# Payload-A.net
KiCad netlist of a schematic drawn in EAGLE
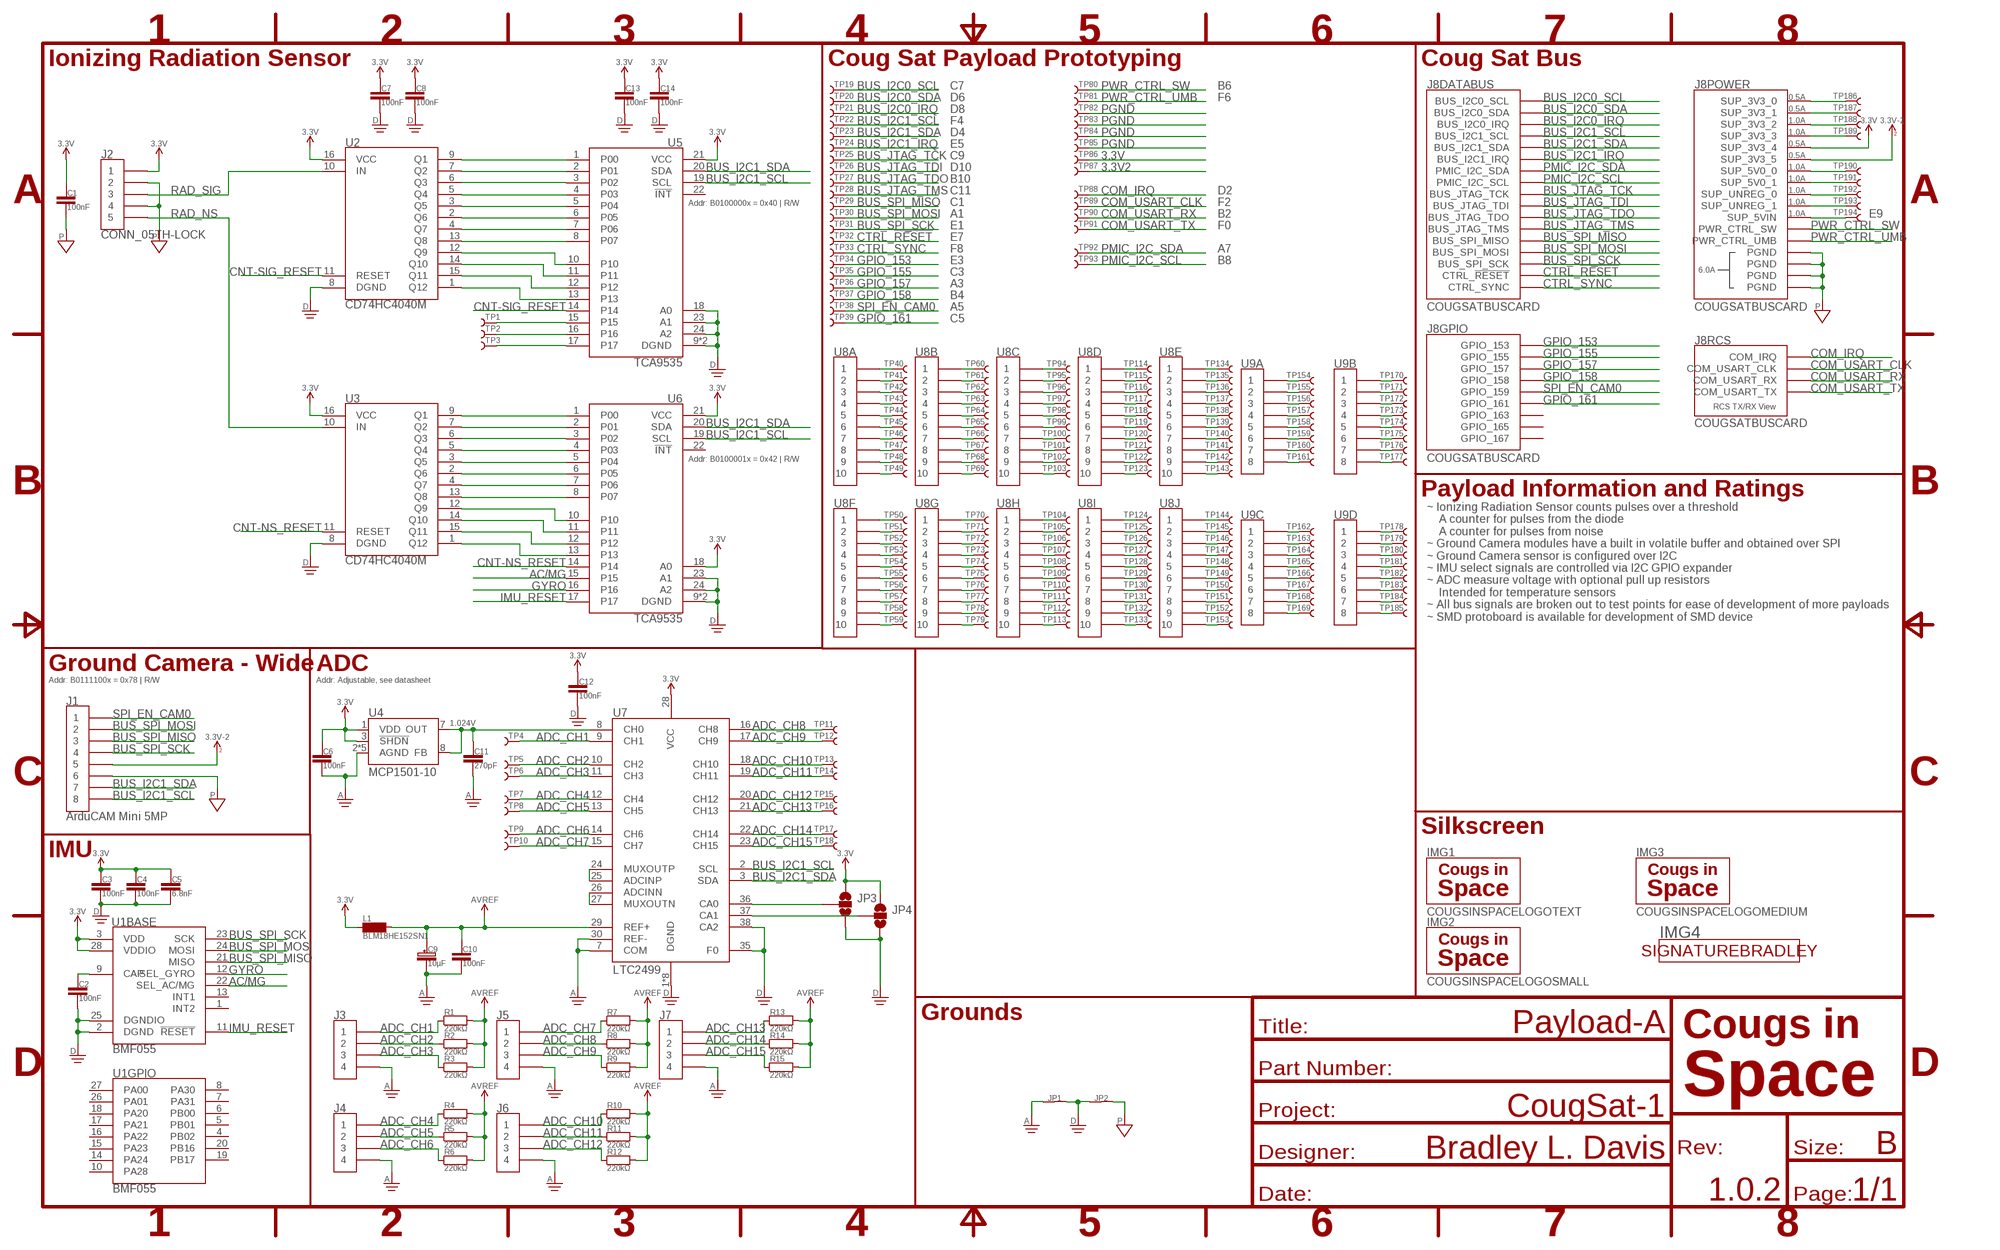
[diagram p0: schematic, sheet 1]

(export (version "E")
  (design (tool "Eeschema 10.0.6"))
  (components
    (comp (ref "C1")
      (value "100nF")
      (footprint "eagle-import:1608")
      (libsource (lib "eagle-import") (part "CAPACITOR1608"))
    )
    (comp (ref "C2")
      (value "100nF")
      (footprint "eagle-import:1608")
      (libsource (lib "eagle-import") (part "CougsInSpace_497568_CAPACITOR1608"))
    )
    (comp (ref "C3")
      (value "100nF")
      (footprint "eagle-import:1608")
      (libsource (lib "eagle-import") (part "CougsInSpace_497568_CAPACITOR1608"))
    )
    (comp (ref "C4")
      (value "100nF")
      (footprint "eagle-import:1608")
      (libsource (lib "eagle-import") (part "CougsInSpace_497568_CAPACITOR1608"))
    )
    (comp (ref "C5")
      (value "6.8nF")
      (footprint "eagle-import:1608")
      (libsource (lib "eagle-import") (part "CougsInSpace_497568_CAPACITOR1608"))
    )
    (comp (ref "C6")
      (value "100nF")
      (footprint "eagle-import:1608")
      (libsource (lib "eagle-import") (part "CougsInSpace_497568_CAPACITOR1608"))
    )
    (comp (ref "C7")
      (value "100nF")
      (footprint "eagle-import:1608")
      (libsource (lib "eagle-import") (part "CAPACITOR1608"))
    )
    (comp (ref "C8")
      (value "100nF")
      (footprint "eagle-import:1608")
      (libsource (lib "eagle-import") (part "CAPACITOR1608"))
    )
    (comp (ref "C9")
      (value "10µF")
      (footprint "eagle-import:4028-POL")
      (libsource (lib "eagle-import") (part "CAPACITOR-POLARIZED4028"))
    )
    (comp (ref "C10")
      (value "100nF")
      (footprint "eagle-import:1608")
      (libsource (lib "eagle-import") (part "CougsInSpace_497568_CAPACITOR1608"))
    )
    (comp (ref "C11")
      (value "270pF")
      (footprint "eagle-import:1608")
      (libsource (lib "eagle-import") (part "CougsInSpace_497568_CAPACITOR1608"))
    )
    (comp (ref "C12")
      (value "100nF")
      (footprint "eagle-import:3216")
      (libsource (lib "eagle-import") (part "CougsInSpace_497568_CAPACITOR3216"))
    )
    (comp (ref "C13")
      (value "100nF")
      (footprint "eagle-import:1608")
      (libsource (lib "eagle-import") (part "CAPACITOR1608"))
    )
    (comp (ref "C14")
      (value "100nF")
      (footprint "eagle-import:1608")
      (libsource (lib "eagle-import") (part "CAPACITOR1608"))
    )
    (comp (ref "IMG1")
      (value "COUGSINSPACELOGOTEXT")
      (footprint "eagle-import:COUGSINSPACETEXT")
      (libsource (lib "eagle-import") (part "COUGSINSPACELOGOTEXT"))
    )
    (comp (ref "IMG2")
      (value "COUGSINSPACELOGOSMALL")
      (footprint "eagle-import:COUGSINSPACELOGO_SMALL")
      (libsource (lib "eagle-import") (part "COUGSINSPACELOGOSMALL"))
    )
    (comp (ref "IMG3")
      (value "COUGSINSPACELOGOMEDIUM")
      (footprint "eagle-import:COUGSINSPACELOGO_MEDIUM")
      (libsource (lib "eagle-import") (part "COUGSINSPACELOGOMEDIUM"))
    )
    (comp (ref "IMG4")
      (value "SIGNATUREBRADLEY")
      (footprint "eagle-import:SIGNATURE-BRADLEY")
      (libsource (lib "eagle-import") (part "SIGNATUREBRADLEY"))
    )
    (comp (ref "J1")
      (value "ArduCAM Mini 5MP")
      (footprint "eagle-import:1X08_LOCK")
      (libsource (lib "eagle-import") (part "CONN_08TH-LOCK"))
    )
    (comp (ref "J2")
      (value "CONN_05TH-LOCK")
      (footprint "eagle-import:1X05_LOCK")
      (libsource (lib "eagle-import") (part "CONN_05TH-LOCK"))
    )
    (comp (ref "J3")
      (value "CONN_04PICOLOCK1.5MM")
      (footprint "eagle-import:1X04_PICOLOCK1.5MM")
      (libsource (lib "eagle-import") (part "CONN_04PICOLOCK1.5MM"))
    )
    (comp (ref "J4")
      (value "CONN_04PICOLOCK1.5MM")
      (footprint "eagle-import:1X04_PICOLOCK1.5MM")
      (libsource (lib "eagle-import") (part "CONN_04PICOLOCK1.5MM"))
    )
    (comp (ref "J5")
      (value "CONN_04PICOLOCK1.5MM")
      (footprint "eagle-import:1X04_PICOLOCK1.5MM")
      (libsource (lib "eagle-import") (part "CONN_04PICOLOCK1.5MM"))
    )
    (comp (ref "J6")
      (value "CONN_04PICOLOCK1.5MM")
      (footprint "eagle-import:1X04_PICOLOCK1.5MM")
      (libsource (lib "eagle-import") (part "CONN_04PICOLOCK1.5MM"))
    )
    (comp (ref "J7")
      (value "CONN_04PICOLOCK1.5MM")
      (footprint "eagle-import:1X04_PICOLOCK1.5MM")
      (libsource (lib "eagle-import") (part "CONN_04PICOLOCK1.5MM"))
    )
    (comp (ref "J8")
      (value "COUGSATBUSCARD")
      (footprint "eagle-import:COUGSATBUS_MALE-SODIMM")
      (libsource (lib "eagle-import") (part "COUGSATBUSCARD"))
    )
    (comp (ref "JP1")
      (value "SHORTCIRCUIT1608JUMPER")
      (footprint "eagle-import:1608")
      (libsource (lib "eagle-import") (part "SHORTCIRCUIT1608JUMPER"))
    )
    (comp (ref "JP2")
      (value "SHORTCIRCUIT1608JUMPER")
      (footprint "eagle-import:1608")
      (libsource (lib "eagle-import") (part "SHORTCIRCUIT1608JUMPER"))
    )
    (comp (ref "JP3")
      (value "JUMPER-SMT_3_NO_SILK")
      (footprint "eagle-import:SMT-JUMPER_3_NO_SILK")
      (libsource (lib "eagle-import") (part "JUMPER-SMT_3_NO_SILK"))
    )
    (comp (ref "JP4")
      (value "JUMPER-SMT_3_NO_SILK")
      (footprint "eagle-import:SMT-JUMPER_3_NO_SILK")
      (libsource (lib "eagle-import") (part "JUMPER-SMT_3_NO_SILK"))
    )
    (comp (ref "L1")
      (value "BLM18HE152SN1")
      (footprint "eagle-import:1608")
      (libsource (lib "eagle-import") (part "INDUCTOR1608"))
    )
    (comp (ref "R1")
      (value "220kΩ")
      (footprint "eagle-import:1608")
      (libsource (lib "eagle-import") (part "RESISTOR1608"))
    )
    (comp (ref "R2")
      (value "220kΩ")
      (footprint "eagle-import:1608")
      (libsource (lib "eagle-import") (part "RESISTOR1608"))
    )
    (comp (ref "R3")
      (value "220kΩ")
      (footprint "eagle-import:1608")
      (libsource (lib "eagle-import") (part "RESISTOR1608"))
    )
    (comp (ref "R4")
      (value "220kΩ")
      (footprint "eagle-import:1608")
      (libsource (lib "eagle-import") (part "RESISTOR1608"))
    )
    (comp (ref "R5")
      (value "220kΩ")
      (footprint "eagle-import:1608")
      (libsource (lib "eagle-import") (part "RESISTOR1608"))
    )
    (comp (ref "R6")
      (value "220kΩ")
      (footprint "eagle-import:1608")
      (libsource (lib "eagle-import") (part "RESISTOR1608"))
    )
    (comp (ref "R7")
      (value "220kΩ")
      (footprint "eagle-import:1608")
      (libsource (lib "eagle-import") (part "RESISTOR1608"))
    )
    (comp (ref "R8")
      (value "220kΩ")
      (footprint "eagle-import:1608")
      (libsource (lib "eagle-import") (part "RESISTOR1608"))
    )
    (comp (ref "R9")
      (value "220kΩ")
      (footprint "eagle-import:1608")
      (libsource (lib "eagle-import") (part "RESISTOR1608"))
    )
    (comp (ref "R10")
      (value "220kΩ")
      (footprint "eagle-import:1608")
      (libsource (lib "eagle-import") (part "RESISTOR1608"))
    )
    (comp (ref "R11")
      (value "220kΩ")
      (footprint "eagle-import:1608")
      (libsource (lib "eagle-import") (part "RESISTOR1608"))
    )
    (comp (ref "R12")
      (value "220kΩ")
      (footprint "eagle-import:1608")
      (libsource (lib "eagle-import") (part "RESISTOR1608"))
    )
    (comp (ref "R13")
      (value "220kΩ")
      (footprint "eagle-import:1608")
      (libsource (lib "eagle-import") (part "RESISTOR1608"))
    )
    (comp (ref "R14")
      (value "220kΩ")
      (footprint "eagle-import:1608")
      (libsource (lib "eagle-import") (part "RESISTOR1608"))
    )
    (comp (ref "R15")
      (value "220kΩ")
      (footprint "eagle-import:1608")
      (libsource (lib "eagle-import") (part "RESISTOR1608"))
    )
    (comp (ref "TP1")
      (value "TEST-POINT1.25MM")
      (footprint "eagle-import:PAD1.25X1.25")
      (libsource (lib "eagle-import") (part "TEST-POINT1.25MM"))
    )
    (comp (ref "TP2")
      (value "TEST-POINT1.25MM")
      (footprint "eagle-import:PAD1.25X1.25")
      (libsource (lib "eagle-import") (part "TEST-POINT1.25MM"))
    )
    (comp (ref "TP3")
      (value "TEST-POINT1.25MM")
      (footprint "eagle-import:PAD1.25X1.25")
      (libsource (lib "eagle-import") (part "TEST-POINT1.25MM"))
    )
    (comp (ref "TP4")
      (value "TEST-POINT1.25MM")
      (footprint "eagle-import:PAD1.25X1.25")
      (libsource (lib "eagle-import") (part "TEST-POINT1.25MM"))
    )
    (comp (ref "TP5")
      (value "TEST-POINT1.25MM")
      (footprint "eagle-import:PAD1.25X1.25")
      (libsource (lib "eagle-import") (part "TEST-POINT1.25MM"))
    )
    (comp (ref "TP6")
      (value "TEST-POINT1.25MM")
      (footprint "eagle-import:PAD1.25X1.25")
      (libsource (lib "eagle-import") (part "TEST-POINT1.25MM"))
    )
    (comp (ref "TP7")
      (value "TEST-POINT1.25MM")
      (footprint "eagle-import:PAD1.25X1.25")
      (libsource (lib "eagle-import") (part "TEST-POINT1.25MM"))
    )
    (comp (ref "TP8")
      (value "TEST-POINT1.25MM")
      (footprint "eagle-import:PAD1.25X1.25")
      (libsource (lib "eagle-import") (part "TEST-POINT1.25MM"))
    )
    (comp (ref "TP9")
      (value "TEST-POINT1.25MM")
      (footprint "eagle-import:PAD1.25X1.25")
      (libsource (lib "eagle-import") (part "TEST-POINT1.25MM"))
    )
    (comp (ref "TP10")
      (value "TEST-POINT1.25MM")
      (footprint "eagle-import:PAD1.25X1.25")
      (libsource (lib "eagle-import") (part "TEST-POINT1.25MM"))
    )
    (comp (ref "TP11")
      (value "TEST-POINT1.25MM")
      (footprint "eagle-import:PAD1.25X1.25")
      (libsource (lib "eagle-import") (part "TEST-POINT1.25MM"))
    )
    (comp (ref "TP12")
      (value "TEST-POINT1.25MM")
      (footprint "eagle-import:PAD1.25X1.25")
      (libsource (lib "eagle-import") (part "TEST-POINT1.25MM"))
    )
    (comp (ref "TP13")
      (value "TEST-POINT1.25MM")
      (footprint "eagle-import:PAD1.25X1.25")
      (libsource (lib "eagle-import") (part "TEST-POINT1.25MM"))
    )
    (comp (ref "TP14")
      (value "TEST-POINT1.25MM")
      (footprint "eagle-import:PAD1.25X1.25")
      (libsource (lib "eagle-import") (part "TEST-POINT1.25MM"))
    )
    (comp (ref "TP15")
      (value "TEST-POINT1.25MM")
      (footprint "eagle-import:PAD1.25X1.25")
      (libsource (lib "eagle-import") (part "TEST-POINT1.25MM"))
    )
    (comp (ref "TP16")
      (value "TEST-POINT1.25MM")
      (footprint "eagle-import:PAD1.25X1.25")
      (libsource (lib "eagle-import") (part "TEST-POINT1.25MM"))
    )
    (comp (ref "TP17")
      (value "TEST-POINT1.25MM")
      (footprint "eagle-import:PAD1.25X1.25")
      (libsource (lib "eagle-import") (part "TEST-POINT1.25MM"))
    )
    (comp (ref "TP18")
      (value "TEST-POINT1.25MM")
      (footprint "eagle-import:PAD1.25X1.25")
      (libsource (lib "eagle-import") (part "TEST-POINT1.25MM"))
    )
    (comp (ref "TP19")
      (value "TEST-POINT1.25MM")
      (footprint "eagle-import:PAD1.25X1.25")
      (libsource (lib "eagle-import") (part "TEST-POINT1.25MM"))
    )
    (comp (ref "TP20")
      (value "TEST-POINT1.25MM")
      (footprint "eagle-import:PAD1.25X1.25")
      (libsource (lib "eagle-import") (part "TEST-POINT1.25MM"))
    )
    (comp (ref "TP21")
      (value "TEST-POINT1.25MM")
      (footprint "eagle-import:PAD1.25X1.25")
      (libsource (lib "eagle-import") (part "TEST-POINT1.25MM"))
    )
    (comp (ref "TP22")
      (value "TEST-POINT1.25MM")
      (footprint "eagle-import:PAD1.25X1.25")
      (libsource (lib "eagle-import") (part "TEST-POINT1.25MM"))
    )
    (comp (ref "TP23")
      (value "TEST-POINT1.25MM")
      (footprint "eagle-import:PAD1.25X1.25")
      (libsource (lib "eagle-import") (part "TEST-POINT1.25MM"))
    )
    (comp (ref "TP24")
      (value "TEST-POINT1.25MM")
      (footprint "eagle-import:PAD1.25X1.25")
      (libsource (lib "eagle-import") (part "TEST-POINT1.25MM"))
    )
    (comp (ref "TP25")
      (value "TEST-POINT1.25MM")
      (footprint "eagle-import:PAD1.25X1.25")
      (libsource (lib "eagle-import") (part "TEST-POINT1.25MM"))
    )
    (comp (ref "TP26")
      (value "TEST-POINT1.25MM")
      (footprint "eagle-import:PAD1.25X1.25")
      (libsource (lib "eagle-import") (part "TEST-POINT1.25MM"))
    )
    (comp (ref "TP27")
      (value "TEST-POINT1.25MM")
      (footprint "eagle-import:PAD1.25X1.25")
      (libsource (lib "eagle-import") (part "TEST-POINT1.25MM"))
    )
    (comp (ref "TP28")
      (value "TEST-POINT1.25MM")
      (footprint "eagle-import:PAD1.25X1.25")
      (libsource (lib "eagle-import") (part "TEST-POINT1.25MM"))
    )
    (comp (ref "TP29")
      (value "TEST-POINT1.25MM")
      (footprint "eagle-import:PAD1.25X1.25")
      (libsource (lib "eagle-import") (part "TEST-POINT1.25MM"))
    )
    (comp (ref "TP30")
      (value "TEST-POINT1.25MM")
      (footprint "eagle-import:PAD1.25X1.25")
      (libsource (lib "eagle-import") (part "TEST-POINT1.25MM"))
    )
    (comp (ref "TP31")
      (value "TEST-POINT1.25MM")
      (footprint "eagle-import:PAD1.25X1.25")
      (libsource (lib "eagle-import") (part "TEST-POINT1.25MM"))
    )
    (comp (ref "TP32")
      (value "TEST-POINT1.25MM")
      (footprint "eagle-import:PAD1.25X1.25")
      (libsource (lib "eagle-import") (part "TEST-POINT1.25MM"))
    )
    (comp (ref "TP33")
      (value "TEST-POINT1.25MM")
      (footprint "eagle-import:PAD1.25X1.25")
      (libsource (lib "eagle-import") (part "TEST-POINT1.25MM"))
    )
    (comp (ref "TP34")
      (value "TEST-POINT1.25MM")
      (footprint "eagle-import:PAD1.25X1.25")
      (libsource (lib "eagle-import") (part "TEST-POINT1.25MM"))
    )
    (comp (ref "TP35")
      (value "TEST-POINT1.25MM")
      (footprint "eagle-import:PAD1.25X1.25")
      (libsource (lib "eagle-import") (part "TEST-POINT1.25MM"))
    )
    (comp (ref "TP36")
      (value "TEST-POINT1.25MM")
      (footprint "eagle-import:PAD1.25X1.25")
      (libsource (lib "eagle-import") (part "TEST-POINT1.25MM"))
    )
    (comp (ref "TP37")
      (value "TEST-POINT1.25MM")
      (footprint "eagle-import:PAD1.25X1.25")
      (libsource (lib "eagle-import") (part "TEST-POINT1.25MM"))
    )
    (comp (ref "TP38")
      (value "TEST-POINT1.25MM")
      (footprint "eagle-import:PAD1.25X1.25")
      (libsource (lib "eagle-import") (part "TEST-POINT1.25MM"))
    )
    (comp (ref "TP39")
      (value "TEST-POINT1.25MM")
      (footprint "eagle-import:PAD1.25X1.25")
      (libsource (lib "eagle-import") (part "TEST-POINT1.25MM"))
    )
    (comp (ref "TP40")
      (value "TEST-POINT1MM")
      (footprint "eagle-import:PAD1X1")
      (libsource (lib "eagle-import") (part "TEST-POINT1MM"))
    )
    (comp (ref "TP41")
      (value "TEST-POINT1MM")
      (footprint "eagle-import:PAD1X1")
      (libsource (lib "eagle-import") (part "TEST-POINT1MM"))
    )
    (comp (ref "TP42")
      (value "TEST-POINT1MM")
      (footprint "eagle-import:PAD1X1")
      (libsource (lib "eagle-import") (part "TEST-POINT1MM"))
    )
    (comp (ref "TP43")
      (value "TEST-POINT1MM")
      (footprint "eagle-import:PAD1X1")
      (libsource (lib "eagle-import") (part "TEST-POINT1MM"))
    )
    (comp (ref "TP44")
      (value "TEST-POINT1MM")
      (footprint "eagle-import:PAD1X1")
      (libsource (lib "eagle-import") (part "TEST-POINT1MM"))
    )
    (comp (ref "TP45")
      (value "TEST-POINT1MM")
      (footprint "eagle-import:PAD1X1")
      (libsource (lib "eagle-import") (part "TEST-POINT1MM"))
    )
    (comp (ref "TP46")
      (value "TEST-POINT1MM")
      (footprint "eagle-import:PAD1X1")
      (libsource (lib "eagle-import") (part "TEST-POINT1MM"))
    )
    (comp (ref "TP47")
      (value "TEST-POINT1MM")
      (footprint "eagle-import:PAD1X1")
      (libsource (lib "eagle-import") (part "TEST-POINT1MM"))
    )
    (comp (ref "TP48")
      (value "TEST-POINT1MM")
      (footprint "eagle-import:PAD1X1")
      (libsource (lib "eagle-import") (part "TEST-POINT1MM"))
    )
    (comp (ref "TP49")
      (value "TEST-POINT1MM")
      (footprint "eagle-import:PAD1X1")
      (libsource (lib "eagle-import") (part "TEST-POINT1MM"))
    )
    (comp (ref "TP50")
      (value "TEST-POINT1MM")
      (footprint "eagle-import:PAD1X1")
      (libsource (lib "eagle-import") (part "TEST-POINT1MM"))
    )
    (comp (ref "TP51")
      (value "TEST-POINT1MM")
      (footprint "eagle-import:PAD1X1")
      (libsource (lib "eagle-import") (part "TEST-POINT1MM"))
    )
    (comp (ref "TP52")
      (value "TEST-POINT1MM")
      (footprint "eagle-import:PAD1X1")
      (libsource (lib "eagle-import") (part "TEST-POINT1MM"))
    )
    (comp (ref "TP53")
      (value "TEST-POINT1MM")
      (footprint "eagle-import:PAD1X1")
      (libsource (lib "eagle-import") (part "TEST-POINT1MM"))
    )
    (comp (ref "TP54")
      (value "TEST-POINT1MM")
      (footprint "eagle-import:PAD1X1")
      (libsource (lib "eagle-import") (part "TEST-POINT1MM"))
    )
    (comp (ref "TP55")
      (value "TEST-POINT1MM")
      (footprint "eagle-import:PAD1X1")
      (libsource (lib "eagle-import") (part "TEST-POINT1MM"))
    )
    (comp (ref "TP56")
      (value "TEST-POINT1MM")
      (footprint "eagle-import:PAD1X1")
      (libsource (lib "eagle-import") (part "TEST-POINT1MM"))
    )
    (comp (ref "TP57")
      (value "TEST-POINT1MM")
      (footprint "eagle-import:PAD1X1")
      (libsource (lib "eagle-import") (part "TEST-POINT1MM"))
    )
    (comp (ref "TP58")
      (value "TEST-POINT1MM")
      (footprint "eagle-import:PAD1X1")
      (libsource (lib "eagle-import") (part "TEST-POINT1MM"))
    )
    (comp (ref "TP59")
      (value "TEST-POINT1MM")
      (footprint "eagle-import:PAD1X1")
      (libsource (lib "eagle-import") (part "TEST-POINT1MM"))
    )
    (comp (ref "TP60")
      (value "TEST-POINT1MM")
      (footprint "eagle-import:PAD1X1")
      (libsource (lib "eagle-import") (part "TEST-POINT1MM"))
    )
    (comp (ref "TP61")
      (value "TEST-POINT1MM")
      (footprint "eagle-import:PAD1X1")
      (libsource (lib "eagle-import") (part "TEST-POINT1MM"))
    )
    (comp (ref "TP62")
      (value "TEST-POINT1MM")
      (footprint "eagle-import:PAD1X1")
      (libsource (lib "eagle-import") (part "TEST-POINT1MM"))
    )
    (comp (ref "TP63")
      (value "TEST-POINT1MM")
      (footprint "eagle-import:PAD1X1")
      (libsource (lib "eagle-import") (part "TEST-POINT1MM"))
    )
    (comp (ref "TP64")
      (value "TEST-POINT1MM")
      (footprint "eagle-import:PAD1X1")
      (libsource (lib "eagle-import") (part "TEST-POINT1MM"))
    )
    (comp (ref "TP65")
      (value "TEST-POINT1MM")
      (footprint "eagle-import:PAD1X1")
      (libsource (lib "eagle-import") (part "TEST-POINT1MM"))
    )
    (comp (ref "TP66")
      (value "TEST-POINT1MM")
      (footprint "eagle-import:PAD1X1")
      (libsource (lib "eagle-import") (part "TEST-POINT1MM"))
    )
    (comp (ref "TP67")
      (value "TEST-POINT1MM")
      (footprint "eagle-import:PAD1X1")
      (libsource (lib "eagle-import") (part "TEST-POINT1MM"))
    )
    (comp (ref "TP68")
      (value "TEST-POINT1MM")
      (footprint "eagle-import:PAD1X1")
      (libsource (lib "eagle-import") (part "TEST-POINT1MM"))
    )
    (comp (ref "TP69")
      (value "TEST-POINT1MM")
      (footprint "eagle-import:PAD1X1")
      (libsource (lib "eagle-import") (part "TEST-POINT1MM"))
    )
    (comp (ref "TP70")
      (value "TEST-POINT1MM")
      (footprint "eagle-import:PAD1X1")
      (libsource (lib "eagle-import") (part "TEST-POINT1MM"))
    )
    (comp (ref "TP71")
      (value "TEST-POINT1MM")
      (footprint "eagle-import:PAD1X1")
      (libsource (lib "eagle-import") (part "TEST-POINT1MM"))
    )
    (comp (ref "TP72")
      (value "TEST-POINT1MM")
      (footprint "eagle-import:PAD1X1")
      (libsource (lib "eagle-import") (part "TEST-POINT1MM"))
    )
    (comp (ref "TP73")
      (value "TEST-POINT1MM")
      (footprint "eagle-import:PAD1X1")
      (libsource (lib "eagle-import") (part "TEST-POINT1MM"))
    )
    (comp (ref "TP74")
      (value "TEST-POINT1MM")
      (footprint "eagle-import:PAD1X1")
      (libsource (lib "eagle-import") (part "TEST-POINT1MM"))
    )
    (comp (ref "TP75")
      (value "TEST-POINT1MM")
      (footprint "eagle-import:PAD1X1")
      (libsource (lib "eagle-import") (part "TEST-POINT1MM"))
    )
    (comp (ref "TP76")
      (value "TEST-POINT1MM")
      (footprint "eagle-import:PAD1X1")
      (libsource (lib "eagle-import") (part "TEST-POINT1MM"))
    )
    (comp (ref "TP77")
      (value "TEST-POINT1MM")
      (footprint "eagle-import:PAD1X1")
      (libsource (lib "eagle-import") (part "TEST-POINT1MM"))
    )
    (comp (ref "TP78")
      (value "TEST-POINT1MM")
      (footprint "eagle-import:PAD1X1")
      (libsource (lib "eagle-import") (part "TEST-POINT1MM"))
    )
    (comp (ref "TP79")
      (value "TEST-POINT1MM")
      (footprint "eagle-import:PAD1X1")
      (libsource (lib "eagle-import") (part "TEST-POINT1MM"))
    )
    (comp (ref "TP80")
      (value "TEST-POINT1.25MM")
      (footprint "eagle-import:PAD1.25X1.25")
      (libsource (lib "eagle-import") (part "TEST-POINT1.25MM"))
    )
    (comp (ref "TP81")
      (value "TEST-POINT1.25MM")
      (footprint "eagle-import:PAD1.25X1.25")
      (libsource (lib "eagle-import") (part "TEST-POINT1.25MM"))
    )
    (comp (ref "TP82")
      (value "TEST-POINT1.25MM")
      (footprint "eagle-import:PAD1.25X1.25")
      (libsource (lib "eagle-import") (part "TEST-POINT1.25MM"))
    )
    (comp (ref "TP83")
      (value "TEST-POINT1.25MM")
      (footprint "eagle-import:PAD1.25X1.25")
      (libsource (lib "eagle-import") (part "TEST-POINT1.25MM"))
    )
    (comp (ref "TP84")
      (value "TEST-POINT1.25MM")
      (footprint "eagle-import:PAD1.25X1.25")
      (libsource (lib "eagle-import") (part "TEST-POINT1.25MM"))
    )
    (comp (ref "TP85")
      (value "TEST-POINT1.25MM")
      (footprint "eagle-import:PAD1.25X1.25")
      (libsource (lib "eagle-import") (part "TEST-POINT1.25MM"))
    )
    (comp (ref "TP86")
      (value "TEST-POINT1.25MM")
      (footprint "eagle-import:PAD1.25X1.25")
      (libsource (lib "eagle-import") (part "TEST-POINT1.25MM"))
    )
    (comp (ref "TP87")
      (value "TEST-POINT1.25MM")
      (footprint "eagle-import:PAD1.25X1.25")
      (libsource (lib "eagle-import") (part "TEST-POINT1.25MM"))
    )
    (comp (ref "TP88")
      (value "TEST-POINT1.25MM")
      (footprint "eagle-import:PAD1.25X1.25")
      (libsource (lib "eagle-import") (part "TEST-POINT1.25MM"))
    )
    (comp (ref "TP89")
      (value "TEST-POINT1.25MM")
      (footprint "eagle-import:PAD1.25X1.25")
      (libsource (lib "eagle-import") (part "TEST-POINT1.25MM"))
    )
    (comp (ref "TP90")
      (value "TEST-POINT1.25MM")
      (footprint "eagle-import:PAD1.25X1.25")
      (libsource (lib "eagle-import") (part "TEST-POINT1.25MM"))
    )
    (comp (ref "TP91")
      (value "TEST-POINT1.25MM")
      (footprint "eagle-import:PAD1.25X1.25")
      (libsource (lib "eagle-import") (part "TEST-POINT1.25MM"))
    )
    (comp (ref "TP92")
      (value "TEST-POINT1.25MM")
      (footprint "eagle-import:PAD1.25X1.25")
      (libsource (lib "eagle-import") (part "TEST-POINT1.25MM"))
    )
    (comp (ref "TP93")
      (value "TEST-POINT1.25MM")
      (footprint "eagle-import:PAD1.25X1.25")
      (libsource (lib "eagle-import") (part "TEST-POINT1.25MM"))
    )
    (comp (ref "TP94")
      (value "TEST-POINT1MM")
      (footprint "eagle-import:PAD1X1")
      (libsource (lib "eagle-import") (part "TEST-POINT1MM"))
    )
    (comp (ref "TP95")
      (value "TEST-POINT1MM")
      (footprint "eagle-import:PAD1X1")
      (libsource (lib "eagle-import") (part "TEST-POINT1MM"))
    )
    (comp (ref "TP96")
      (value "TEST-POINT1MM")
      (footprint "eagle-import:PAD1X1")
      (libsource (lib "eagle-import") (part "TEST-POINT1MM"))
    )
    (comp (ref "TP97")
      (value "TEST-POINT1MM")
      (footprint "eagle-import:PAD1X1")
      (libsource (lib "eagle-import") (part "TEST-POINT1MM"))
    )
    (comp (ref "TP98")
      (value "TEST-POINT1MM")
      (footprint "eagle-import:PAD1X1")
      (libsource (lib "eagle-import") (part "TEST-POINT1MM"))
    )
    (comp (ref "TP99")
      (value "TEST-POINT1MM")
      (footprint "eagle-import:PAD1X1")
      (libsource (lib "eagle-import") (part "TEST-POINT1MM"))
    )
    (comp (ref "TP100")
      (value "TEST-POINT1MM")
      (footprint "eagle-import:PAD1X1")
      (libsource (lib "eagle-import") (part "TEST-POINT1MM"))
    )
    (comp (ref "TP101")
      (value "TEST-POINT1MM")
      (footprint "eagle-import:PAD1X1")
      (libsource (lib "eagle-import") (part "TEST-POINT1MM"))
    )
    (comp (ref "TP102")
      (value "TEST-POINT1MM")
      (footprint "eagle-import:PAD1X1")
      (libsource (lib "eagle-import") (part "TEST-POINT1MM"))
    )
    (comp (ref "TP103")
      (value "TEST-POINT1MM")
      (footprint "eagle-import:PAD1X1")
      (libsource (lib "eagle-import") (part "TEST-POINT1MM"))
    )
    (comp (ref "TP104")
      (value "TEST-POINT1MM")
      (footprint "eagle-import:PAD1X1")
      (libsource (lib "eagle-import") (part "TEST-POINT1MM"))
    )
    (comp (ref "TP105")
      (value "TEST-POINT1MM")
      (footprint "eagle-import:PAD1X1")
      (libsource (lib "eagle-import") (part "TEST-POINT1MM"))
    )
    (comp (ref "TP106")
      (value "TEST-POINT1MM")
      (footprint "eagle-import:PAD1X1")
      (libsource (lib "eagle-import") (part "TEST-POINT1MM"))
    )
    (comp (ref "TP107")
      (value "TEST-POINT1MM")
      (footprint "eagle-import:PAD1X1")
      (libsource (lib "eagle-import") (part "TEST-POINT1MM"))
    )
    (comp (ref "TP108")
      (value "TEST-POINT1MM")
      (footprint "eagle-import:PAD1X1")
      (libsource (lib "eagle-import") (part "TEST-POINT1MM"))
    )
    (comp (ref "TP109")
      (value "TEST-POINT1MM")
      (footprint "eagle-import:PAD1X1")
      (libsource (lib "eagle-import") (part "TEST-POINT1MM"))
    )
    (comp (ref "TP110")
      (value "TEST-POINT1MM")
      (footprint "eagle-import:PAD1X1")
      (libsource (lib "eagle-import") (part "TEST-POINT1MM"))
    )
    (comp (ref "TP111")
      (value "TEST-POINT1MM")
      (footprint "eagle-import:PAD1X1")
      (libsource (lib "eagle-import") (part "TEST-POINT1MM"))
    )
    (comp (ref "TP112")
      (value "TEST-POINT1MM")
      (footprint "eagle-import:PAD1X1")
      (libsource (lib "eagle-import") (part "TEST-POINT1MM"))
    )
    (comp (ref "TP113")
      (value "TEST-POINT1MM")
      (footprint "eagle-import:PAD1X1")
      (libsource (lib "eagle-import") (part "TEST-POINT1MM"))
    )
    (comp (ref "TP114")
      (value "TEST-POINT1MM")
      (footprint "eagle-import:PAD1X1")
      (libsource (lib "eagle-import") (part "TEST-POINT1MM"))
    )
    (comp (ref "TP115")
      (value "TEST-POINT1MM")
      (footprint "eagle-import:PAD1X1")
      (libsource (lib "eagle-import") (part "TEST-POINT1MM"))
    )
    (comp (ref "TP116")
      (value "TEST-POINT1MM")
      (footprint "eagle-import:PAD1X1")
      (libsource (lib "eagle-import") (part "TEST-POINT1MM"))
    )
    (comp (ref "TP117")
      (value "TEST-POINT1MM")
      (footprint "eagle-import:PAD1X1")
      (libsource (lib "eagle-import") (part "TEST-POINT1MM"))
    )
    (comp (ref "TP118")
      (value "TEST-POINT1MM")
      (footprint "eagle-import:PAD1X1")
      (libsource (lib "eagle-import") (part "TEST-POINT1MM"))
    )
    (comp (ref "TP119")
      (value "TEST-POINT1MM")
      (footprint "eagle-import:PAD1X1")
      (libsource (lib "eagle-import") (part "TEST-POINT1MM"))
    )
    (comp (ref "TP120")
      (value "TEST-POINT1MM")
      (footprint "eagle-import:PAD1X1")
      (libsource (lib "eagle-import") (part "TEST-POINT1MM"))
    )
    (comp (ref "TP121")
      (value "TEST-POINT1MM")
      (footprint "eagle-import:PAD1X1")
      (libsource (lib "eagle-import") (part "TEST-POINT1MM"))
    )
    (comp (ref "TP122")
      (value "TEST-POINT1MM")
      (footprint "eagle-import:PAD1X1")
      (libsource (lib "eagle-import") (part "TEST-POINT1MM"))
    )
    (comp (ref "TP123")
      (value "TEST-POINT1MM")
      (footprint "eagle-import:PAD1X1")
      (libsource (lib "eagle-import") (part "TEST-POINT1MM"))
    )
    (comp (ref "TP124")
      (value "TEST-POINT1MM")
      (footprint "eagle-import:PAD1X1")
      (libsource (lib "eagle-import") (part "TEST-POINT1MM"))
    )
    (comp (ref "TP125")
      (value "TEST-POINT1MM")
      (footprint "eagle-import:PAD1X1")
      (libsource (lib "eagle-import") (part "TEST-POINT1MM"))
    )
    (comp (ref "TP126")
      (value "TEST-POINT1MM")
      (footprint "eagle-import:PAD1X1")
      (libsource (lib "eagle-import") (part "TEST-POINT1MM"))
    )
    (comp (ref "TP127")
      (value "TEST-POINT1MM")
      (footprint "eagle-import:PAD1X1")
      (libsource (lib "eagle-import") (part "TEST-POINT1MM"))
    )
    (comp (ref "TP128")
      (value "TEST-POINT1MM")
      (footprint "eagle-import:PAD1X1")
      (libsource (lib "eagle-import") (part "TEST-POINT1MM"))
    )
    (comp (ref "TP129")
      (value "TEST-POINT1MM")
      (footprint "eagle-import:PAD1X1")
      (libsource (lib "eagle-import") (part "TEST-POINT1MM"))
    )
    (comp (ref "TP130")
      (value "TEST-POINT1MM")
      (footprint "eagle-import:PAD1X1")
      (libsource (lib "eagle-import") (part "TEST-POINT1MM"))
    )
    (comp (ref "TP131")
      (value "TEST-POINT1MM")
      (footprint "eagle-import:PAD1X1")
      (libsource (lib "eagle-import") (part "TEST-POINT1MM"))
    )
    (comp (ref "TP132")
      (value "TEST-POINT1MM")
      (footprint "eagle-import:PAD1X1")
      (libsource (lib "eagle-import") (part "TEST-POINT1MM"))
    )
    (comp (ref "TP133")
      (value "TEST-POINT1MM")
      (footprint "eagle-import:PAD1X1")
      (libsource (lib "eagle-import") (part "TEST-POINT1MM"))
    )
    (comp (ref "TP134")
      (value "TEST-POINT1MM")
      (footprint "eagle-import:PAD1X1")
      (libsource (lib "eagle-import") (part "TEST-POINT1MM"))
    )
    (comp (ref "TP135")
      (value "TEST-POINT1MM")
      (footprint "eagle-import:PAD1X1")
      (libsource (lib "eagle-import") (part "TEST-POINT1MM"))
    )
    (comp (ref "TP136")
      (value "TEST-POINT1MM")
      (footprint "eagle-import:PAD1X1")
      (libsource (lib "eagle-import") (part "TEST-POINT1MM"))
    )
    (comp (ref "TP137")
      (value "TEST-POINT1MM")
      (footprint "eagle-import:PAD1X1")
      (libsource (lib "eagle-import") (part "TEST-POINT1MM"))
    )
    (comp (ref "TP138")
      (value "TEST-POINT1MM")
      (footprint "eagle-import:PAD1X1")
      (libsource (lib "eagle-import") (part "TEST-POINT1MM"))
    )
    (comp (ref "TP139")
      (value "TEST-POINT1MM")
      (footprint "eagle-import:PAD1X1")
      (libsource (lib "eagle-import") (part "TEST-POINT1MM"))
    )
    (comp (ref "TP140")
      (value "TEST-POINT1MM")
      (footprint "eagle-import:PAD1X1")
      (libsource (lib "eagle-import") (part "TEST-POINT1MM"))
    )
    (comp (ref "TP141")
      (value "TEST-POINT1MM")
      (footprint "eagle-import:PAD1X1")
      (libsource (lib "eagle-import") (part "TEST-POINT1MM"))
    )
    (comp (ref "TP142")
      (value "TEST-POINT1MM")
      (footprint "eagle-import:PAD1X1")
      (libsource (lib "eagle-import") (part "TEST-POINT1MM"))
    )
    (comp (ref "TP143")
      (value "TEST-POINT1MM")
      (footprint "eagle-import:PAD1X1")
      (libsource (lib "eagle-import") (part "TEST-POINT1MM"))
    )
    (comp (ref "TP144")
      (value "TEST-POINT1MM")
      (footprint "eagle-import:PAD1X1")
      (libsource (lib "eagle-import") (part "TEST-POINT1MM"))
    )
    (comp (ref "TP145")
      (value "TEST-POINT1MM")
      (footprint "eagle-import:PAD1X1")
      (libsource (lib "eagle-import") (part "TEST-POINT1MM"))
    )
    (comp (ref "TP146")
      (value "TEST-POINT1MM")
      (footprint "eagle-import:PAD1X1")
      (libsource (lib "eagle-import") (part "TEST-POINT1MM"))
    )
    (comp (ref "TP147")
      (value "TEST-POINT1MM")
      (footprint "eagle-import:PAD1X1")
      (libsource (lib "eagle-import") (part "TEST-POINT1MM"))
    )
    (comp (ref "TP148")
      (value "TEST-POINT1MM")
      (footprint "eagle-import:PAD1X1")
      (libsource (lib "eagle-import") (part "TEST-POINT1MM"))
    )
    (comp (ref "TP149")
      (value "TEST-POINT1MM")
      (footprint "eagle-import:PAD1X1")
      (libsource (lib "eagle-import") (part "TEST-POINT1MM"))
    )
    (comp (ref "TP150")
      (value "TEST-POINT1MM")
      (footprint "eagle-import:PAD1X1")
      (libsource (lib "eagle-import") (part "TEST-POINT1MM"))
    )
    (comp (ref "TP151")
      (value "TEST-POINT1MM")
      (footprint "eagle-import:PAD1X1")
      (libsource (lib "eagle-import") (part "TEST-POINT1MM"))
    )
    (comp (ref "TP152")
      (value "TEST-POINT1MM")
      (footprint "eagle-import:PAD1X1")
      (libsource (lib "eagle-import") (part "TEST-POINT1MM"))
    )
    (comp (ref "TP153")
      (value "TEST-POINT1MM")
      (footprint "eagle-import:PAD1X1")
      (libsource (lib "eagle-import") (part "TEST-POINT1MM"))
    )
    (comp (ref "TP154")
      (value "TEST-POINT1MM")
      (footprint "eagle-import:PAD1X1")
      (libsource (lib "eagle-import") (part "TEST-POINT1MM"))
    )
    (comp (ref "TP155")
      (value "TEST-POINT1MM")
      (footprint "eagle-import:PAD1X1")
      (libsource (lib "eagle-import") (part "TEST-POINT1MM"))
    )
    (comp (ref "TP156")
      (value "TEST-POINT1MM")
      (footprint "eagle-import:PAD1X1")
      (libsource (lib "eagle-import") (part "TEST-POINT1MM"))
    )
    (comp (ref "TP157")
      (value "TEST-POINT1MM")
      (footprint "eagle-import:PAD1X1")
      (libsource (lib "eagle-import") (part "TEST-POINT1MM"))
    )
    (comp (ref "TP158")
      (value "TEST-POINT1MM")
      (footprint "eagle-import:PAD1X1")
      (libsource (lib "eagle-import") (part "TEST-POINT1MM"))
    )
    (comp (ref "TP159")
      (value "TEST-POINT1MM")
      (footprint "eagle-import:PAD1X1")
      (libsource (lib "eagle-import") (part "TEST-POINT1MM"))
    )
    (comp (ref "TP160")
      (value "TEST-POINT1MM")
      (footprint "eagle-import:PAD1X1")
      (libsource (lib "eagle-import") (part "TEST-POINT1MM"))
    )
    (comp (ref "TP161")
      (value "TEST-POINT1MM")
      (footprint "eagle-import:PAD1X1")
      (libsource (lib "eagle-import") (part "TEST-POINT1MM"))
    )
    (comp (ref "TP162")
      (value "TEST-POINT1MM")
      (footprint "eagle-import:PAD1X1")
      (libsource (lib "eagle-import") (part "TEST-POINT1MM"))
    )
    (comp (ref "TP163")
      (value "TEST-POINT1MM")
      (footprint "eagle-import:PAD1X1")
      (libsource (lib "eagle-import") (part "TEST-POINT1MM"))
    )
    (comp (ref "TP164")
      (value "TEST-POINT1MM")
      (footprint "eagle-import:PAD1X1")
      (libsource (lib "eagle-import") (part "TEST-POINT1MM"))
    )
    (comp (ref "TP165")
      (value "TEST-POINT1MM")
      (footprint "eagle-import:PAD1X1")
      (libsource (lib "eagle-import") (part "TEST-POINT1MM"))
    )
    (comp (ref "TP166")
      (value "TEST-POINT1MM")
      (footprint "eagle-import:PAD1X1")
      (libsource (lib "eagle-import") (part "TEST-POINT1MM"))
    )
    (comp (ref "TP167")
      (value "TEST-POINT1MM")
      (footprint "eagle-import:PAD1X1")
      (libsource (lib "eagle-import") (part "TEST-POINT1MM"))
    )
    (comp (ref "TP168")
      (value "TEST-POINT1MM")
      (footprint "eagle-import:PAD1X1")
      (libsource (lib "eagle-import") (part "TEST-POINT1MM"))
    )
    (comp (ref "TP169")
      (value "TEST-POINT1MM")
      (footprint "eagle-import:PAD1X1")
      (libsource (lib "eagle-import") (part "TEST-POINT1MM"))
    )
    (comp (ref "TP170")
      (value "TEST-POINT1MM")
      (footprint "eagle-import:PAD1X1")
      (libsource (lib "eagle-import") (part "TEST-POINT1MM"))
    )
    (comp (ref "TP171")
      (value "TEST-POINT1MM")
      (footprint "eagle-import:PAD1X1")
      (libsource (lib "eagle-import") (part "TEST-POINT1MM"))
    )
    (comp (ref "TP172")
      (value "TEST-POINT1MM")
      (footprint "eagle-import:PAD1X1")
      (libsource (lib "eagle-import") (part "TEST-POINT1MM"))
    )
    (comp (ref "TP173")
      (value "TEST-POINT1MM")
      (footprint "eagle-import:PAD1X1")
      (libsource (lib "eagle-import") (part "TEST-POINT1MM"))
    )
    (comp (ref "TP174")
      (value "TEST-POINT1MM")
      (footprint "eagle-import:PAD1X1")
      (libsource (lib "eagle-import") (part "TEST-POINT1MM"))
    )
    (comp (ref "TP175")
      (value "TEST-POINT1MM")
      (footprint "eagle-import:PAD1X1")
      (libsource (lib "eagle-import") (part "TEST-POINT1MM"))
    )
    (comp (ref "TP176")
      (value "TEST-POINT1MM")
      (footprint "eagle-import:PAD1X1")
      (libsource (lib "eagle-import") (part "TEST-POINT1MM"))
    )
    (comp (ref "TP177")
      (value "TEST-POINT1MM")
      (footprint "eagle-import:PAD1X1")
      (libsource (lib "eagle-import") (part "TEST-POINT1MM"))
    )
    (comp (ref "TP178")
      (value "TEST-POINT1MM")
      (footprint "eagle-import:PAD1X1")
      (libsource (lib "eagle-import") (part "TEST-POINT1MM"))
    )
    (comp (ref "TP179")
      (value "TEST-POINT1MM")
      (footprint "eagle-import:PAD1X1")
      (libsource (lib "eagle-import") (part "TEST-POINT1MM"))
    )
    (comp (ref "TP180")
      (value "TEST-POINT1MM")
      (footprint "eagle-import:PAD1X1")
      (libsource (lib "eagle-import") (part "TEST-POINT1MM"))
    )
    (comp (ref "TP181")
      (value "TEST-POINT1MM")
      (footprint "eagle-import:PAD1X1")
      (libsource (lib "eagle-import") (part "TEST-POINT1MM"))
    )
    (comp (ref "TP182")
      (value "TEST-POINT1MM")
      (footprint "eagle-import:PAD1X1")
      (libsource (lib "eagle-import") (part "TEST-POINT1MM"))
    )
    (comp (ref "TP183")
      (value "TEST-POINT1MM")
      (footprint "eagle-import:PAD1X1")
      (libsource (lib "eagle-import") (part "TEST-POINT1MM"))
    )
    (comp (ref "TP184")
      (value "TEST-POINT1MM")
      (footprint "eagle-import:PAD1X1")
      (libsource (lib "eagle-import") (part "TEST-POINT1MM"))
    )
    (comp (ref "TP185")
      (value "TEST-POINT1MM")
      (footprint "eagle-import:PAD1X1")
      (libsource (lib "eagle-import") (part "TEST-POINT1MM"))
    )
    (comp (ref "TP186")
      (value "TEST-POINT1.25MM")
      (footprint "eagle-import:PAD1.25X1.25")
      (libsource (lib "eagle-import") (part "TEST-POINT1.25MM"))
    )
    (comp (ref "TP187")
      (value "TEST-POINT1.25MM")
      (footprint "eagle-import:PAD1.25X1.25")
      (libsource (lib "eagle-import") (part "TEST-POINT1.25MM"))
    )
    (comp (ref "TP188")
      (value "TEST-POINT1.25MM")
      (footprint "eagle-import:PAD1.25X1.25")
      (libsource (lib "eagle-import") (part "TEST-POINT1.25MM"))
    )
    (comp (ref "TP189")
      (value "TEST-POINT1.25MM")
      (footprint "eagle-import:PAD1.25X1.25")
      (libsource (lib "eagle-import") (part "TEST-POINT1.25MM"))
    )
    (comp (ref "TP190")
      (value "TEST-POINT1.25MM")
      (footprint "eagle-import:PAD1.25X1.25")
      (libsource (lib "eagle-import") (part "TEST-POINT1.25MM"))
    )
    (comp (ref "TP191")
      (value "TEST-POINT1.25MM")
      (footprint "eagle-import:PAD1.25X1.25")
      (libsource (lib "eagle-import") (part "TEST-POINT1.25MM"))
    )
    (comp (ref "TP192")
      (value "TEST-POINT1.25MM")
      (footprint "eagle-import:PAD1.25X1.25")
      (libsource (lib "eagle-import") (part "TEST-POINT1.25MM"))
    )
    (comp (ref "TP193")
      (value "TEST-POINT1.25MM")
      (footprint "eagle-import:PAD1.25X1.25")
      (libsource (lib "eagle-import") (part "TEST-POINT1.25MM"))
    )
    (comp (ref "TP194")
      (value "TEST-POINT1.25MM")
      (footprint "eagle-import:PAD1.25X1.25")
      (libsource (lib "eagle-import") (part "TEST-POINT1.25MM"))
    )
    (comp (ref "U1")
      (value "BMF055")
      (footprint "eagle-import:LGA28-4X5MM")
      (libsource (lib "eagle-import") (part "BMF055"))
    )
    (comp (ref "U2")
      (value "CD74HC4040M")
      (footprint "eagle-import:SO16")
      (libsource (lib "eagle-import") (part "COUNTER-RIPPLE_12STAGESO16"))
    )
    (comp (ref "U3")
      (value "CD74HC4040M")
      (footprint "eagle-import:SO16")
      (libsource (lib "eagle-import") (part "COUNTER-RIPPLE_12STAGESO16"))
    )
    (comp (ref "U4")
      (value "MCP1501-10")
      (footprint "eagle-import:WDFN8-2X2")
      (libsource (lib "eagle-import") (part "VOLTAGEREFERENCEWDFN8"))
    )
    (comp (ref "U5")
      (value "TCA9535")
      (footprint "eagle-import:QFN24-4X4")
      (libsource (lib "eagle-import") (part "IOEXPANDER_16BITQFN24"))
    )
    (comp (ref "U6")
      (value "TCA9535")
      (footprint "eagle-import:QFN24-4X4")
      (libsource (lib "eagle-import") (part "IOEXPANDER_16BITQFN24"))
    )
    (comp (ref "U7")
      (value "LTC2499")
      (footprint "eagle-import:QFN38-5X7")
      (libsource (lib "eagle-import") (part "LTC2499"))
    )
    (comp (ref "U8")
      (value "PROTOBOARD-100SMD0.5MM")
      (footprint "eagle-import:PROTOBOARD-SMD0.5MM")
      (libsource (lib "eagle-import") (part "PROTOBOARD-100SMD0.5MM"))
    )
    (comp (ref "U9")
      (value "PROTOBOARD-32SOIC")
      (footprint "eagle-import:PROTOBOARD-SOIC")
      (libsource (lib "eagle-import") (part "PROTOBOARD-32SOIC"))
    )
  )
  (nets
    (net (code "1") (name "/AC{slash}MG") (class "Default")
      (node (ref "U1") (pin "22") (pinfunction "SEL_AC/MG_22") (pintype "input"))
      (node (ref "U6") (pin "15") (pinfunction "P15_15") (pintype "bidirectional"))
    )
    (net (code "2") (name "/ADC_CH1") (class "Default")
      (node (ref "J3") (pin "1") (pinfunction "1_1") (pintype "bidirectional"))
      (node (ref "R1") (pin "1") (pinfunction "1_1") (pintype "passive"))
      (node (ref "TP4") (pin "1") (pinfunction "1_1") (pintype "bidirectional"))
      (node (ref "U7") (pin "9") (pinfunction "CH1_9") (pintype "passive"))
    )
    (net (code "3") (name "/ADC_CH2") (class "Default")
      (node (ref "J3") (pin "2") (pinfunction "2_2") (pintype "bidirectional"))
      (node (ref "R2") (pin "1") (pinfunction "1_1") (pintype "passive"))
      (node (ref "TP5") (pin "1") (pinfunction "1_1") (pintype "bidirectional"))
      (node (ref "U7") (pin "10") (pinfunction "CH2_10") (pintype "passive"))
    )
    (net (code "4") (name "/ADC_CH3") (class "Default")
      (node (ref "J3") (pin "3") (pinfunction "3_3") (pintype "bidirectional"))
      (node (ref "R3") (pin "1") (pinfunction "1_1") (pintype "passive"))
      (node (ref "TP6") (pin "1") (pinfunction "1_1") (pintype "bidirectional"))
      (node (ref "U7") (pin "11") (pinfunction "CH3_11") (pintype "passive"))
    )
    (net (code "5") (name "/ADC_CH4") (class "Default")
      (node (ref "J4") (pin "1") (pinfunction "1_1") (pintype "bidirectional"))
      (node (ref "R4") (pin "1") (pinfunction "1_1") (pintype "passive"))
      (node (ref "TP7") (pin "1") (pinfunction "1_1") (pintype "bidirectional"))
      (node (ref "U7") (pin "12") (pinfunction "CH4_12") (pintype "passive"))
    )
    (net (code "6") (name "/ADC_CH5") (class "Default")
      (node (ref "J4") (pin "2") (pinfunction "2_2") (pintype "bidirectional"))
      (node (ref "R5") (pin "1") (pinfunction "1_1") (pintype "passive"))
      (node (ref "TP8") (pin "1") (pinfunction "1_1") (pintype "bidirectional"))
      (node (ref "U7") (pin "13") (pinfunction "CH5_13") (pintype "passive"))
    )
    (net (code "7") (name "/ADC_CH6") (class "Default")
      (node (ref "J4") (pin "3") (pinfunction "3_3") (pintype "bidirectional"))
      (node (ref "R6") (pin "1") (pinfunction "1_1") (pintype "passive"))
      (node (ref "TP9") (pin "1") (pinfunction "1_1") (pintype "bidirectional"))
      (node (ref "U7") (pin "14") (pinfunction "CH6_14") (pintype "passive"))
    )
    (net (code "8") (name "/ADC_CH7") (class "Default")
      (node (ref "J5") (pin "1") (pinfunction "1_1") (pintype "bidirectional"))
      (node (ref "R7") (pin "1") (pinfunction "1_1") (pintype "passive"))
      (node (ref "TP10") (pin "1") (pinfunction "1_1") (pintype "bidirectional"))
      (node (ref "U7") (pin "15") (pinfunction "CH7_15") (pintype "passive"))
    )
    (net (code "9") (name "/ADC_CH8") (class "Default")
      (node (ref "J5") (pin "2") (pinfunction "2_2") (pintype "bidirectional"))
      (node (ref "R8") (pin "1") (pinfunction "1_1") (pintype "passive"))
      (node (ref "TP11") (pin "1") (pinfunction "1_1") (pintype "bidirectional"))
      (node (ref "U7") (pin "16") (pinfunction "CH8_16") (pintype "passive"))
    )
    (net (code "10") (name "/ADC_CH9") (class "Default")
      (node (ref "J5") (pin "3") (pinfunction "3_3") (pintype "bidirectional"))
      (node (ref "R9") (pin "1") (pinfunction "1_1") (pintype "passive"))
      (node (ref "TP12") (pin "1") (pinfunction "1_1") (pintype "bidirectional"))
      (node (ref "U7") (pin "17") (pinfunction "CH9_17") (pintype "passive"))
    )
    (net (code "11") (name "/ADC_CH10") (class "Default")
      (node (ref "J6") (pin "1") (pinfunction "1_1") (pintype "bidirectional"))
      (node (ref "R10") (pin "1") (pinfunction "1_1") (pintype "passive"))
      (node (ref "TP13") (pin "1") (pinfunction "1_1") (pintype "bidirectional"))
      (node (ref "U7") (pin "18") (pinfunction "CH10_18") (pintype "passive"))
    )
    (net (code "12") (name "/ADC_CH11") (class "Default")
      (node (ref "J6") (pin "2") (pinfunction "2_2") (pintype "bidirectional"))
      (node (ref "R11") (pin "1") (pinfunction "1_1") (pintype "passive"))
      (node (ref "TP14") (pin "1") (pinfunction "1_1") (pintype "bidirectional"))
      (node (ref "U7") (pin "19") (pinfunction "CH11_19") (pintype "passive"))
    )
    (net (code "13") (name "/ADC_CH12") (class "Default")
      (node (ref "J6") (pin "3") (pinfunction "3_3") (pintype "bidirectional"))
      (node (ref "R12") (pin "1") (pinfunction "1_1") (pintype "passive"))
      (node (ref "TP15") (pin "1") (pinfunction "1_1") (pintype "bidirectional"))
      (node (ref "U7") (pin "20") (pinfunction "CH12_20") (pintype "passive"))
    )
    (net (code "14") (name "/ADC_CH13") (class "Default")
      (node (ref "J7") (pin "1") (pinfunction "1_1") (pintype "bidirectional"))
      (node (ref "R13") (pin "1") (pinfunction "1_1") (pintype "passive"))
      (node (ref "TP16") (pin "1") (pinfunction "1_1") (pintype "bidirectional"))
      (node (ref "U7") (pin "21") (pinfunction "CH13_21") (pintype "passive"))
    )
    (net (code "15") (name "/ADC_CH14") (class "Default")
      (node (ref "J7") (pin "2") (pinfunction "2_2") (pintype "bidirectional"))
      (node (ref "R14") (pin "1") (pinfunction "1_1") (pintype "passive"))
      (node (ref "TP17") (pin "1") (pinfunction "1_1") (pintype "bidirectional"))
      (node (ref "U7") (pin "22") (pinfunction "CH14_22") (pintype "passive"))
    )
    (net (code "16") (name "/ADC_CH15") (class "Default")
      (node (ref "J7") (pin "3") (pinfunction "3_3") (pintype "bidirectional"))
      (node (ref "R15") (pin "1") (pinfunction "1_1") (pintype "passive"))
      (node (ref "TP18") (pin "1") (pinfunction "1_1") (pintype "bidirectional"))
      (node (ref "U7") (pin "23") (pinfunction "CH15_23") (pintype "passive"))
    )
    (net (code "17") (name "/BUS_I2C0_IRQ") (class "Default")
      (node (ref "J8") (pin "177") (pinfunction "BUS_I2C0_IRQ_177") (pintype "bidirectional"))
      (node (ref "J8") (pin "179") (pinfunction "BUS_I2C0_IRQ_179") (pintype "bidirectional"))
      (node (ref "TP21") (pin "1") (pinfunction "1_1") (pintype "bidirectional"))
    )
    (net (code "18") (name "/BUS_I2C0_SCL") (class "Default")
      (node (ref "J8") (pin "173") (pinfunction "BUS_I2C0_SCL_173") (pintype "bidirectional"))
      (node (ref "J8") (pin "175") (pinfunction "BUS_I2C0_SCL_175") (pintype "bidirectional"))
      (node (ref "TP19") (pin "1") (pinfunction "1_1") (pintype "bidirectional"))
    )
    (net (code "19") (name "/BUS_I2C0_SDA") (class "Default")
      (node (ref "J8") (pin "169") (pinfunction "BUS_I2C0_SDA_169") (pintype "bidirectional"))
      (node (ref "J8") (pin "171") (pinfunction "BUS_I2C0_SDA_171") (pintype "bidirectional"))
      (node (ref "TP20") (pin "1") (pinfunction "1_1") (pintype "bidirectional"))
    )
    (net (code "20") (name "/BUS_I2C1_IRQ") (class "Default")
      (node (ref "J8") (pin "164") (pinfunction "BUS_I2C1_IRQ_164") (pintype "bidirectional"))
      (node (ref "TP24") (pin "1") (pinfunction "1_1") (pintype "bidirectional"))
    )
    (net (code "21") (name "/BUS_I2C1_SCL") (class "Default")
      (node (ref "J1") (pin "8") (pinfunction "8_8") (pintype "bidirectional"))
      (node (ref "J8") (pin "160") (pinfunction "BUS_I2C1_SCL_160") (pintype "bidirectional"))
      (node (ref "TP22") (pin "1") (pinfunction "1_1") (pintype "bidirectional"))
      (node (ref "U5") (pin "19") (pinfunction "SCL_19") (pintype "bidirectional"))
      (node (ref "U6") (pin "19") (pinfunction "SCL_19") (pintype "bidirectional"))
      (node (ref "U7") (pin "2") (pinfunction "SCL_2") (pintype "bidirectional"))
    )
    (net (code "22") (name "/BUS_I2C1_SDA") (class "Default")
      (node (ref "J1") (pin "7") (pinfunction "7_7") (pintype "bidirectional"))
      (node (ref "J8") (pin "162") (pinfunction "BUS_I2C1_SDA_162") (pintype "bidirectional"))
      (node (ref "TP23") (pin "1") (pinfunction "1_1") (pintype "bidirectional"))
      (node (ref "U5") (pin "20") (pinfunction "SDA_20") (pintype "bidirectional"))
      (node (ref "U6") (pin "20") (pinfunction "SDA_20") (pintype "bidirectional"))
      (node (ref "U7") (pin "3") (pinfunction "SDA_3") (pintype "bidirectional"))
    )
    (net (code "23") (name "/BUS_JTAG_TCK") (class "Default")
      (node (ref "J8") (pin "185") (pinfunction "BUS_JTAG_TCK_185") (pintype "bidirectional"))
      (node (ref "J8") (pin "187") (pinfunction "BUS_JTAG_TCK_187") (pintype "bidirectional"))
      (node (ref "TP25") (pin "1") (pinfunction "1_1") (pintype "bidirectional"))
    )
    (net (code "24") (name "/BUS_JTAG_TDI") (class "Default")
      (node (ref "J8") (pin "189") (pinfunction "BUS_JTAG_TDI_189") (pintype "bidirectional"))
      (node (ref "J8") (pin "191") (pinfunction "BUS_JTAG_TDI_191") (pintype "bidirectional"))
      (node (ref "TP26") (pin "1") (pinfunction "1_1") (pintype "bidirectional"))
    )
    (net (code "25") (name "/BUS_JTAG_TDO") (class "Default")
      (node (ref "J8") (pin "193") (pinfunction "BUS_JTAG_TDO_193") (pintype "bidirectional"))
      (node (ref "J8") (pin "195") (pinfunction "BUS_JTAG_TDO_195") (pintype "bidirectional"))
      (node (ref "TP27") (pin "1") (pinfunction "1_1") (pintype "bidirectional"))
    )
    (net (code "26") (name "/BUS_JTAG_TMS") (class "Default")
      (node (ref "J8") (pin "197") (pinfunction "BUS_JTAG_TMS_197") (pintype "bidirectional"))
      (node (ref "J8") (pin "199") (pinfunction "BUS_JTAG_TMS_199") (pintype "bidirectional"))
      (node (ref "TP28") (pin "1") (pinfunction "1_1") (pintype "bidirectional"))
    )
    (net (code "27") (name "/BUS_SPI_MISO") (class "Default")
      (node (ref "J1") (pin "3") (pinfunction "3_3") (pintype "bidirectional"))
      (node (ref "J8") (pin "145") (pinfunction "BUS_SPI_MISO_145") (pintype "bidirectional"))
      (node (ref "J8") (pin "147") (pinfunction "BUS_SPI_MISO_147") (pintype "bidirectional"))
      (node (ref "TP29") (pin "1") (pinfunction "1_1") (pintype "bidirectional"))
      (node (ref "U1") (pin "21") (pinfunction "MISO_21") (pintype "output"))
    )
    (net (code "28") (name "/BUS_SPI_MOSI") (class "Default")
      (node (ref "J1") (pin "2") (pinfunction "2_2") (pintype "bidirectional"))
      (node (ref "J8") (pin "149") (pinfunction "BUS_SPI_MOSI_149") (pintype "bidirectional"))
      (node (ref "J8") (pin "151") (pinfunction "BUS_SPI_MOSI_151") (pintype "bidirectional"))
      (node (ref "TP30") (pin "1") (pinfunction "1_1") (pintype "bidirectional"))
      (node (ref "U1") (pin "24") (pinfunction "MOSI_24") (pintype "input"))
    )
    (net (code "29") (name "/BUS_SPI_SCK") (class "Default")
      (node (ref "J1") (pin "4") (pinfunction "4_4") (pintype "bidirectional"))
      (node (ref "J8") (pin "141") (pinfunction "BUS_SPI_SCK_141") (pintype "bidirectional"))
      (node (ref "J8") (pin "143") (pinfunction "BUS_SPI_SCK_143") (pintype "bidirectional"))
      (node (ref "TP31") (pin "1") (pinfunction "1_1") (pintype "bidirectional"))
      (node (ref "U1") (pin "23") (pinfunction "SCK_23") (pintype "input"))
    )
    (net (code "30") (name "/CNT-NS_RESET") (class "Default")
      (node (ref "U3") (pin "11") (pinfunction "RESET_11") (pintype "input"))
      (node (ref "U6") (pin "14") (pinfunction "P14_14") (pintype "bidirectional"))
    )
    (net (code "31") (name "/CNT-SIG_RESET") (class "Default")
      (node (ref "U2") (pin "11") (pinfunction "RESET_11") (pintype "input"))
      (node (ref "U5") (pin "14") (pinfunction "P14_14") (pintype "bidirectional"))
    )
    (net (code "32") (name "/COM_IRQ") (class "Default")
      (node (ref "J8") (pin "154") (pinfunction "COM_IRQ_154") (pintype "bidirectional"))
      (node (ref "J8") (pin "156") (pinfunction "COM_IRQ_156") (pintype "bidirectional"))
      (node (ref "TP88") (pin "1") (pinfunction "1_1") (pintype "bidirectional"))
    )
    (net (code "33") (name "/COM_USART_CLK") (class "Default")
      (node (ref "J8") (pin "150") (pinfunction "COM_USART_CLK_150") (pintype "bidirectional"))
      (node (ref "J8") (pin "152") (pinfunction "COM_USART_CLK_152") (pintype "bidirectional"))
      (node (ref "TP89") (pin "1") (pinfunction "1_1") (pintype "bidirectional"))
    )
    (net (code "34") (name "/COM_USART_RX") (class "Default")
      (node (ref "J8") (pin "146") (pinfunction "COM_USART_RX_146") (pintype "bidirectional"))
      (node (ref "J8") (pin "148") (pinfunction "COM_USART_RX_148") (pintype "bidirectional"))
      (node (ref "TP90") (pin "1") (pinfunction "1_1") (pintype "bidirectional"))
    )
    (net (code "35") (name "/COM_USART_TX") (class "Default")
      (node (ref "J8") (pin "142") (pinfunction "COM_USART_TX_142") (pintype "bidirectional"))
      (node (ref "J8") (pin "144") (pinfunction "COM_USART_TX_144") (pintype "bidirectional"))
      (node (ref "TP91") (pin "1") (pinfunction "1_1") (pintype "bidirectional"))
    )
    (net (code "36") (name "/CTRL_SYNC") (class "Default")
      (node (ref "J8") (pin "178") (pinfunction "CTRL_SYNC_178") (pintype "bidirectional"))
      (node (ref "J8") (pin "180") (pinfunction "CTRL_SYNC_180") (pintype "bidirectional"))
      (node (ref "TP33") (pin "1") (pinfunction "1_1") (pintype "bidirectional"))
    )
    (net (code "37") (name "/CTRL_~{RESET}") (class "Default")
      (node (ref "J8") (pin "174") (pinfunction "CTRL_~{RESET}_174") (pintype "bidirectional"))
      (node (ref "J8") (pin "176") (pinfunction "CTRL_~{RESET}_176") (pintype "bidirectional"))
      (node (ref "TP32") (pin "1") (pinfunction "1_1") (pintype "bidirectional"))
    )
    (net (code "38") (name "/GPIO_153") (class "Default")
      (node (ref "J8") (pin "153") (pinfunction "GPIO_153_153") (pintype "bidirectional"))
      (node (ref "TP34") (pin "1") (pinfunction "1_1") (pintype "bidirectional"))
    )
    (net (code "39") (name "/GPIO_155") (class "Default")
      (node (ref "J8") (pin "155") (pinfunction "GPIO_155_155") (pintype "bidirectional"))
      (node (ref "TP35") (pin "1") (pinfunction "1_1") (pintype "bidirectional"))
    )
    (net (code "40") (name "/GPIO_157") (class "Default")
      (node (ref "J8") (pin "157") (pinfunction "GPIO_157_157") (pintype "bidirectional"))
      (node (ref "TP36") (pin "1") (pinfunction "1_1") (pintype "bidirectional"))
    )
    (net (code "41") (name "/GPIO_158") (class "Default")
      (node (ref "J8") (pin "158") (pinfunction "GPIO_158_158") (pintype "bidirectional"))
      (node (ref "TP37") (pin "1") (pinfunction "1_1") (pintype "bidirectional"))
    )
    (net (code "42") (name "/GPIO_161") (class "Default")
      (node (ref "J8") (pin "161") (pinfunction "GPIO_161_161") (pintype "bidirectional"))
      (node (ref "TP39") (pin "1") (pinfunction "1_1") (pintype "bidirectional"))
    )
    (net (code "43") (name "/GYRO") (class "Default")
      (node (ref "U1") (pin "12") (pinfunction "SEL_GYRO_12") (pintype "input"))
      (node (ref "U6") (pin "16") (pinfunction "P16_16") (pintype "bidirectional"))
    )
    (net (code "44") (name "/IMU_RESET") (class "Default")
      (node (ref "U1") (pin "11") (pinfunction "~{RESET}_11") (pintype "bidirectional"))
      (node (ref "U6") (pin "17") (pinfunction "P17_17") (pintype "bidirectional"))
    )
    (net (code "45") (name "/PMIC_I2C_SCL") (class "Default")
      (node (ref "J8") (pin "183") (pinfunction "PMIC_I2C_SCL_183") (pintype "bidirectional"))
      (node (ref "TP93") (pin "1") (pinfunction "1_1") (pintype "bidirectional"))
    )
    (net (code "46") (name "/PMIC_I2C_SDA") (class "Default")
      (node (ref "J8") (pin "181") (pinfunction "PMIC_I2C_SDA_181") (pintype "bidirectional"))
      (node (ref "TP92") (pin "1") (pinfunction "1_1") (pintype "bidirectional"))
    )
    (net (code "47") (name "/PWR_CTRL_SW") (class "Default")
      (node (ref "J8") (pin "166") (pinfunction "PWR_CTRL_SW_166") (pintype "bidirectional"))
      (node (ref "J8") (pin "168") (pinfunction "PWR_CTRL_SW_168") (pintype "bidirectional"))
      (node (ref "TP80") (pin "1") (pinfunction "1_1") (pintype "bidirectional"))
    )
    (net (code "48") (name "/PWR_CTRL_UMB") (class "Default")
      (node (ref "J8") (pin "170") (pinfunction "PWR_CTRL_UMB_170") (pintype "bidirectional"))
      (node (ref "J8") (pin "172") (pinfunction "PWR_CTRL_UMB_172") (pintype "bidirectional"))
      (node (ref "TP81") (pin "1") (pinfunction "1_1") (pintype "bidirectional"))
    )
    (net (code "49") (name "/RAD_NS") (class "Default")
      (node (ref "J2") (pin "5") (pinfunction "5_5") (pintype "bidirectional"))
      (node (ref "U3") (pin "10") (pinfunction "IN_10") (pintype "input"))
    )
    (net (code "50") (name "/RAD_SIG") (class "Default")
      (node (ref "J2") (pin "3") (pinfunction "3_3") (pintype "bidirectional"))
      (node (ref "U2") (pin "10") (pinfunction "IN_10") (pintype "input"))
    )
    (net (code "51") (name "/SPI_EN_CAM0") (class "Default")
      (node (ref "J1") (pin "1") (pinfunction "1_1") (pintype "bidirectional"))
      (node (ref "J8") (pin "159") (pinfunction "GPIO_159_159") (pintype "bidirectional"))
      (node (ref "TP38") (pin "1") (pinfunction "1_1") (pintype "bidirectional"))
    )
    (net (code "52") (name "3.3V") (class "Default")
      (node (ref "C1") (pin "1") (pinfunction "1_1") (pintype "passive"))
      (node (ref "C12") (pin "1") (pinfunction "1_1") (pintype "passive"))
      (node (ref "C13") (pin "1") (pinfunction "1_1") (pintype "passive"))
      (node (ref "C14") (pin "1") (pinfunction "1_1") (pintype "passive"))
      (node (ref "C3") (pin "1") (pinfunction "1_1") (pintype "passive"))
      (node (ref "C4") (pin "1") (pinfunction "1_1") (pintype "passive"))
      (node (ref "C5") (pin "1") (pinfunction "1_1") (pintype "passive"))
      (node (ref "C6") (pin "1") (pinfunction "1_1") (pintype "passive"))
      (node (ref "C7") (pin "1") (pinfunction "1_1") (pintype "passive"))
      (node (ref "C8") (pin "1") (pinfunction "1_1") (pintype "passive"))
      (node (ref "J2") (pin "1") (pinfunction "1_1") (pintype "bidirectional"))
      (node (ref "J8") (pin "42") (pinfunction "SUP_3V3_4_42") (pintype "power_in"))
      (node (ref "J8") (pin "44") (pinfunction "SUP_3V3_4_44") (pintype "power_in"))
      (node (ref "J8") (pin "46") (pinfunction "SUP_3V3_4_46") (pintype "power_in"))
      (node (ref "J8") (pin "48") (pinfunction "SUP_3V3_4_48") (pintype "power_in"))
      (node (ref "J8") (pin "50") (pinfunction "SUP_3V3_4_50") (pintype "power_in"))
      (node (ref "JP3") (pin "1") (pinfunction "1_1") (pintype "passive"))
      (node (ref "JP4") (pin "1") (pinfunction "1_1") (pintype "passive"))
      (node (ref "L1") (pin "2") (pinfunction "2_2") (pintype "passive"))
      (node (ref "TP86") (pin "1") (pinfunction "1_1") (pintype "bidirectional"))
      (node (ref "U1") (pin "28") (pinfunction "VDDIO_28") (pintype "power_in"))
      (node (ref "U1") (pin "3") (pinfunction "VDD_3") (pintype "power_in"))
      (node (ref "U2") (pin "16") (pinfunction "VCC_16") (pintype "power_in"))
      (node (ref "U3") (pin "16") (pinfunction "VCC_16") (pintype "power_in"))
      (node (ref "U4") (pin "1") (pinfunction "VDD_1") (pintype "input"))
      (node (ref "U4") (pin "3") (pinfunction "~{SHDN}_3") (pintype "input"))
      (node (ref "U5") (pin "21") (pinfunction "VCC_21") (pintype "power_in"))
      (node (ref "U6") (pin "18") (pinfunction "A0_18") (pintype "passive"))
      (node (ref "U6") (pin "21") (pinfunction "VCC_21") (pintype "power_in"))
      (node (ref "U7") (pin "28") (pinfunction "VCC_28") (pintype "power_in"))
    )
    (net (code "53") (name "3.3V-2") (class "Default")
      (node (ref "J1") (pin "5") (pinfunction "5_5") (pintype "bidirectional"))
      (node (ref "J8") (pin "52") (pinfunction "SUP_3V3_5_52") (pintype "power_in"))
      (node (ref "J8") (pin "54") (pinfunction "SUP_3V3_5_54") (pintype "power_in"))
      (node (ref "J8") (pin "56") (pinfunction "SUP_3V3_5_56") (pintype "power_in"))
      (node (ref "J8") (pin "58") (pinfunction "SUP_3V3_5_58") (pintype "power_in"))
      (node (ref "J8") (pin "60") (pinfunction "SUP_3V3_5_60") (pintype "power_in"))
      (node (ref "TP87") (pin "1") (pinfunction "1_1") (pintype "bidirectional"))
    )
    (net (code "54") (name "AGND") (class "Default")
      (node (ref "C10") (pin "2") (pinfunction "2_2") (pintype "passive"))
      (node (ref "C11") (pin "2") (pinfunction "2_2") (pintype "passive"))
      (node (ref "C6") (pin "2") (pinfunction "2_2") (pintype "passive"))
      (node (ref "C9") (pin "C") (pinfunction "C_C") (pintype "passive"))
      (node (ref "J3") (pin "4") (pinfunction "4_4") (pintype "bidirectional"))
      (node (ref "J4") (pin "4") (pinfunction "4_4") (pintype "bidirectional"))
      (node (ref "J5") (pin "4") (pinfunction "4_4") (pintype "bidirectional"))
      (node (ref "J6") (pin "4") (pinfunction "4_4") (pintype "bidirectional"))
      (node (ref "J7") (pin "4") (pinfunction "4_4") (pintype "bidirectional"))
      (node (ref "JP1") (pin "1") (pinfunction "1_1") (pintype "passive"))
      (node (ref "U4") (pin "2") (pinfunction "AGND_2") (pintype "power_in"))
      (node (ref "U4") (pin "4") (pinfunction "AGND_4") (pintype "power_in"))
      (node (ref "U4") (pin "5") (pinfunction "AGND_5") (pintype "power_in"))
      (node (ref "U4") (pin "6") (pinfunction "AGND_6") (pintype "power_in"))
      (node (ref "U4") (pin "PAD") (pinfunction "AGND_PAD") (pintype "power_in"))
      (node (ref "U7") (pin "30") (pinfunction "REF-_30") (pintype "input"))
      (node (ref "U7") (pin "7") (pinfunction "COM_7") (pintype "input"))
    )
    (net (code "55") (name "AVREF") (class "Default")
      (node (ref "C10") (pin "1") (pinfunction "1_1") (pintype "passive"))
      (node (ref "C9") (pin "A") (pinfunction "A_A") (pintype "passive"))
      (node (ref "L1") (pin "1") (pinfunction "1_1") (pintype "passive"))
      (node (ref "R1") (pin "2") (pinfunction "2_2") (pintype "passive"))
      (node (ref "R10") (pin "2") (pinfunction "2_2") (pintype "passive"))
      (node (ref "R11") (pin "2") (pinfunction "2_2") (pintype "passive"))
      (node (ref "R12") (pin "2") (pinfunction "2_2") (pintype "passive"))
      (node (ref "R13") (pin "2") (pinfunction "2_2") (pintype "passive"))
      (node (ref "R14") (pin "2") (pinfunction "2_2") (pintype "passive"))
      (node (ref "R15") (pin "2") (pinfunction "2_2") (pintype "passive"))
      (node (ref "R2") (pin "2") (pinfunction "2_2") (pintype "passive"))
      (node (ref "R3") (pin "2") (pinfunction "2_2") (pintype "passive"))
      (node (ref "R4") (pin "2") (pinfunction "2_2") (pintype "passive"))
      (node (ref "R5") (pin "2") (pinfunction "2_2") (pintype "passive"))
      (node (ref "R6") (pin "2") (pinfunction "2_2") (pintype "passive"))
      (node (ref "R7") (pin "2") (pinfunction "2_2") (pintype "passive"))
      (node (ref "R8") (pin "2") (pinfunction "2_2") (pintype "passive"))
      (node (ref "R9") (pin "2") (pinfunction "2_2") (pintype "passive"))
      (node (ref "U7") (pin "29") (pinfunction "REF+_29") (pintype "input"))
    )
    (net (code "56") (name "DGND") (class "Default")
      (node (ref "C12") (pin "2") (pinfunction "2_2") (pintype "passive"))
      (node (ref "C13") (pin "2") (pinfunction "2_2") (pintype "passive"))
      (node (ref "C14") (pin "2") (pinfunction "2_2") (pintype "passive"))
      (node (ref "C2") (pin "2") (pinfunction "2_2") (pintype "passive"))
      (node (ref "C3") (pin "2") (pinfunction "2_2") (pintype "passive"))
      (node (ref "C4") (pin "2") (pinfunction "2_2") (pintype "passive"))
      (node (ref "C5") (pin "2") (pinfunction "2_2") (pintype "passive"))
      (node (ref "C7") (pin "2") (pinfunction "2_2") (pintype "passive"))
      (node (ref "C8") (pin "2") (pinfunction "2_2") (pintype "passive"))
      (node (ref "JP1") (pin "2") (pinfunction "2_2") (pintype "passive"))
      (node (ref "JP2") (pin "1") (pinfunction "1_1") (pintype "passive"))
      (node (ref "JP3") (pin "3") (pinfunction "3_3") (pintype "passive"))
      (node (ref "JP4") (pin "3") (pinfunction "3_3") (pintype "passive"))
      (node (ref "U1") (pin "2") (pinfunction "DGND_2") (pintype "power_in"))
      (node (ref "U1") (pin "25") (pinfunction "DGNDIO_25") (pintype "power_in"))
      (node (ref "U2") (pin "8") (pinfunction "DGND_8") (pintype "power_in"))
      (node (ref "U3") (pin "8") (pinfunction "DGND_8") (pintype "power_in"))
      (node (ref "U5") (pin "18") (pinfunction "A0_18") (pintype "passive"))
      (node (ref "U5") (pin "23") (pinfunction "A1_23") (pintype "passive"))
      (node (ref "U5") (pin "24") (pinfunction "A2_24") (pintype "passive"))
      (node (ref "U5") (pin "9") (pinfunction "DGND_9") (pintype "power_in"))
      (node (ref "U5") (pin "PAD") (pinfunction "DGND_PAD") (pintype "power_in"))
      (node (ref "U6") (pin "23") (pinfunction "A1_23") (pintype "passive"))
      (node (ref "U6") (pin "24") (pinfunction "A2_24") (pintype "passive"))
      (node (ref "U6") (pin "9") (pinfunction "DGND_9") (pintype "power_in"))
      (node (ref "U6") (pin "PAD") (pinfunction "DGND_PAD") (pintype "power_in"))
      (node (ref "U7") (pin "1") (pinfunction "DGND_1") (pintype "power_in"))
      (node (ref "U7") (pin "31") (pinfunction "DGND_31") (pintype "power_in"))
      (node (ref "U7") (pin "32") (pinfunction "DGND_32") (pintype "power_in"))
      (node (ref "U7") (pin "33") (pinfunction "DGND_33") (pintype "power_in"))
      (node (ref "U7") (pin "34") (pinfunction "DGND_34") (pintype "power_in"))
      (node (ref "U7") (pin "35") (pinfunction "F0_35") (pintype "passive"))
      (node (ref "U7") (pin "38") (pinfunction "CA2_38") (pintype "bidirectional"))
      (node (ref "U7") (pin "4") (pinfunction "DGND_4") (pintype "power_in"))
      (node (ref "U7") (pin "6") (pinfunction "DGND_6") (pintype "power_in"))
      (node (ref "U7") (pin "PAD") (pinfunction "DGND_PAD") (pintype "power_in"))
    )
    (net (code "57") (name "Net-(J8C-SUP_3V3_0-Pad10)") (class "Default")
      (node (ref "J8") (pin "10") (pinfunction "SUP_3V3_0_10") (pintype "power_in"))
      (node (ref "J8") (pin "2") (pinfunction "SUP_3V3_0_2") (pintype "power_in"))
      (node (ref "J8") (pin "4") (pinfunction "SUP_3V3_0_4") (pintype "power_in"))
      (node (ref "J8") (pin "6") (pinfunction "SUP_3V3_0_6") (pintype "power_in"))
      (node (ref "J8") (pin "8") (pinfunction "SUP_3V3_0_8") (pintype "power_in"))
      (node (ref "TP186") (pin "1") (pinfunction "1_1") (pintype "bidirectional"))
    )
    (net (code "58") (name "Net-(J8C-SUP_3V3_1-Pad12)") (class "Default")
      (node (ref "J8") (pin "12") (pinfunction "SUP_3V3_1_12") (pintype "power_in"))
      (node (ref "J8") (pin "14") (pinfunction "SUP_3V3_1_14") (pintype "power_in"))
      (node (ref "J8") (pin "16") (pinfunction "SUP_3V3_1_16") (pintype "power_in"))
      (node (ref "J8") (pin "18") (pinfunction "SUP_3V3_1_18") (pintype "power_in"))
      (node (ref "J8") (pin "20") (pinfunction "SUP_3V3_1_20") (pintype "power_in"))
      (node (ref "TP187") (pin "1") (pinfunction "1_1") (pintype "bidirectional"))
    )
    (net (code "59") (name "Net-(J8C-SUP_3V3_2-Pad21)") (class "Default")
      (node (ref "J8") (pin "21") (pinfunction "SUP_3V3_2_21") (pintype "power_in"))
      (node (ref "J8") (pin "23") (pinfunction "SUP_3V3_2_23") (pintype "power_in"))
      (node (ref "J8") (pin "25") (pinfunction "SUP_3V3_2_25") (pintype "power_in"))
      (node (ref "J8") (pin "27") (pinfunction "SUP_3V3_2_27") (pintype "power_in"))
      (node (ref "J8") (pin "29") (pinfunction "SUP_3V3_2_29") (pintype "power_in"))
      (node (ref "J8") (pin "31") (pinfunction "SUP_3V3_2_31") (pintype "power_in"))
      (node (ref "J8") (pin "33") (pinfunction "SUP_3V3_2_33") (pintype "power_in"))
      (node (ref "J8") (pin "35") (pinfunction "SUP_3V3_2_35") (pintype "power_in"))
      (node (ref "J8") (pin "37") (pinfunction "SUP_3V3_2_37") (pintype "power_in"))
      (node (ref "J8") (pin "39") (pinfunction "SUP_3V3_2_39") (pintype "power_in"))
      (node (ref "TP188") (pin "1") (pinfunction "1_1") (pintype "bidirectional"))
    )
    (net (code "60") (name "Net-(J8C-SUP_3V3_3-Pad22)") (class "Default")
      (node (ref "J8") (pin "22") (pinfunction "SUP_3V3_3_22") (pintype "power_in"))
      (node (ref "J8") (pin "24") (pinfunction "SUP_3V3_3_24") (pintype "power_in"))
      (node (ref "J8") (pin "26") (pinfunction "SUP_3V3_3_26") (pintype "power_in"))
      (node (ref "J8") (pin "28") (pinfunction "SUP_3V3_3_28") (pintype "power_in"))
      (node (ref "J8") (pin "30") (pinfunction "SUP_3V3_3_30") (pintype "power_in"))
      (node (ref "J8") (pin "32") (pinfunction "SUP_3V3_3_32") (pintype "power_in"))
      (node (ref "J8") (pin "34") (pinfunction "SUP_3V3_3_34") (pintype "power_in"))
      (node (ref "J8") (pin "36") (pinfunction "SUP_3V3_3_36") (pintype "power_in"))
      (node (ref "J8") (pin "38") (pinfunction "SUP_3V3_3_38") (pintype "power_in"))
      (node (ref "J8") (pin "40") (pinfunction "SUP_3V3_3_40") (pintype "power_in"))
      (node (ref "TP189") (pin "1") (pinfunction "1_1") (pintype "bidirectional"))
    )
    (net (code "61") (name "Net-(J8C-SUP_5V0_0-Pad62)") (class "Default")
      (node (ref "J8") (pin "62") (pinfunction "SUP_5V0_0_62") (pintype "power_in"))
      (node (ref "J8") (pin "64") (pinfunction "SUP_5V0_0_64") (pintype "power_in"))
      (node (ref "J8") (pin "66") (pinfunction "SUP_5V0_0_66") (pintype "power_in"))
      (node (ref "J8") (pin "68") (pinfunction "SUP_5V0_0_68") (pintype "power_in"))
      (node (ref "J8") (pin "70") (pinfunction "SUP_5V0_0_70") (pintype "power_in"))
      (node (ref "J8") (pin "72") (pinfunction "SUP_5V0_0_72") (pintype "power_in"))
      (node (ref "J8") (pin "74") (pinfunction "SUP_5V0_0_74") (pintype "power_in"))
      (node (ref "J8") (pin "76") (pinfunction "SUP_5V0_0_76") (pintype "power_in"))
      (node (ref "J8") (pin "78") (pinfunction "SUP_5V0_0_78") (pintype "power_in"))
      (node (ref "J8") (pin "80") (pinfunction "SUP_5V0_0_80") (pintype "power_in"))
      (node (ref "TP190") (pin "1") (pinfunction "1_1") (pintype "bidirectional"))
    )
    (net (code "62") (name "Net-(J8C-SUP_5V0_1-Pad71)") (class "Default")
      (node (ref "J8") (pin "71") (pinfunction "SUP_5V0_1_71") (pintype "power_in"))
      (node (ref "J8") (pin "73") (pinfunction "SUP_5V0_1_73") (pintype "power_in"))
      (node (ref "J8") (pin "75") (pinfunction "SUP_5V0_1_75") (pintype "power_in"))
      (node (ref "J8") (pin "77") (pinfunction "SUP_5V0_1_77") (pintype "power_in"))
      (node (ref "J8") (pin "79") (pinfunction "SUP_5V0_1_79") (pintype "power_in"))
      (node (ref "J8") (pin "81") (pinfunction "SUP_5V0_1_81") (pintype "power_in"))
      (node (ref "J8") (pin "83") (pinfunction "SUP_5V0_1_83") (pintype "power_in"))
      (node (ref "J8") (pin "85") (pinfunction "SUP_5V0_1_85") (pintype "power_in"))
      (node (ref "J8") (pin "87") (pinfunction "SUP_5V0_1_87") (pintype "power_in"))
      (node (ref "J8") (pin "89") (pinfunction "SUP_5V0_1_89") (pintype "power_in"))
      (node (ref "TP191") (pin "1") (pinfunction "1_1") (pintype "bidirectional"))
    )
    (net (code "63") (name "Net-(J8C-SUP_5VIN-Pad182)") (class "Default")
      (node (ref "J8") (pin "182") (pinfunction "SUP_5VIN_182") (pintype "power_in"))
      (node (ref "J8") (pin "184") (pinfunction "SUP_5VIN_184") (pintype "power_in"))
      (node (ref "J8") (pin "186") (pinfunction "SUP_5VIN_186") (pintype "power_in"))
      (node (ref "J8") (pin "188") (pinfunction "SUP_5VIN_188") (pintype "power_in"))
      (node (ref "J8") (pin "190") (pinfunction "SUP_5VIN_190") (pintype "power_in"))
      (node (ref "J8") (pin "192") (pinfunction "SUP_5VIN_192") (pintype "power_in"))
      (node (ref "J8") (pin "194") (pinfunction "SUP_5VIN_194") (pintype "power_in"))
      (node (ref "J8") (pin "196") (pinfunction "SUP_5VIN_196") (pintype "power_in"))
      (node (ref "J8") (pin "198") (pinfunction "SUP_5VIN_198") (pintype "power_in"))
      (node (ref "J8") (pin "200") (pinfunction "SUP_5VIN_200") (pintype "power_in"))
      (node (ref "TP194") (pin "1") (pinfunction "1_1") (pintype "bidirectional"))
    )
    (net (code "64") (name "Net-(J8C-SUP_UNREG_0-Pad101)") (class "Default")
      (node (ref "J8") (pin "101") (pinfunction "SUP_UNREG_0_101") (pintype "power_in"))
      (node (ref "J8") (pin "103") (pinfunction "SUP_UNREG_0_103") (pintype "power_in"))
      (node (ref "J8") (pin "105") (pinfunction "SUP_UNREG_0_105") (pintype "power_in"))
      (node (ref "J8") (pin "107") (pinfunction "SUP_UNREG_0_107") (pintype "power_in"))
      (node (ref "J8") (pin "109") (pinfunction "SUP_UNREG_0_109") (pintype "power_in"))
      (node (ref "J8") (pin "91") (pinfunction "SUP_UNREG_0_91") (pintype "power_in"))
      (node (ref "J8") (pin "93") (pinfunction "SUP_UNREG_0_93") (pintype "power_in"))
      (node (ref "J8") (pin "95") (pinfunction "SUP_UNREG_0_95") (pintype "power_in"))
      (node (ref "J8") (pin "97") (pinfunction "SUP_UNREG_0_97") (pintype "power_in"))
      (node (ref "J8") (pin "99") (pinfunction "SUP_UNREG_0_99") (pintype "power_in"))
      (node (ref "TP192") (pin "1") (pinfunction "1_1") (pintype "bidirectional"))
    )
    (net (code "65") (name "Net-(J8C-SUP_UNREG_1-Pad111)") (class "Default")
      (node (ref "J8") (pin "111") (pinfunction "SUP_UNREG_1_111") (pintype "power_in"))
      (node (ref "J8") (pin "113") (pinfunction "SUP_UNREG_1_113") (pintype "power_in"))
      (node (ref "J8") (pin "115") (pinfunction "SUP_UNREG_1_115") (pintype "power_in"))
      (node (ref "J8") (pin "117") (pinfunction "SUP_UNREG_1_117") (pintype "power_in"))
      (node (ref "J8") (pin "119") (pinfunction "SUP_UNREG_1_119") (pintype "power_in"))
      (node (ref "J8") (pin "121") (pinfunction "SUP_UNREG_1_121") (pintype "power_in"))
      (node (ref "J8") (pin "123") (pinfunction "SUP_UNREG_1_123") (pintype "power_in"))
      (node (ref "J8") (pin "125") (pinfunction "SUP_UNREG_1_125") (pintype "power_in"))
      (node (ref "J8") (pin "127") (pinfunction "SUP_UNREG_1_127") (pintype "power_in"))
      (node (ref "J8") (pin "129") (pinfunction "SUP_UNREG_1_129") (pintype "power_in"))
      (node (ref "TP193") (pin "1") (pinfunction "1_1") (pintype "bidirectional"))
    )
    (net (code "66") (name "Net-(TP40-Pad1)") (class "Default")
      (node (ref "TP40") (pin "1") (pinfunction "1_1") (pintype "bidirectional"))
      (node (ref "U8") (pin "1") (pinfunction "1_1") (pintype "bidirectional"))
    )
    (net (code "67") (name "Net-(TP41-Pad1)") (class "Default")
      (node (ref "TP41") (pin "1") (pinfunction "1_1") (pintype "bidirectional"))
      (node (ref "U8") (pin "2") (pinfunction "2_2") (pintype "bidirectional"))
    )
    (net (code "68") (name "Net-(TP42-Pad1)") (class "Default")
      (node (ref "TP42") (pin "1") (pinfunction "1_1") (pintype "bidirectional"))
      (node (ref "U8") (pin "3") (pinfunction "3_3") (pintype "bidirectional"))
    )
    (net (code "69") (name "Net-(TP43-Pad1)") (class "Default")
      (node (ref "TP43") (pin "1") (pinfunction "1_1") (pintype "bidirectional"))
      (node (ref "U8") (pin "4") (pinfunction "4_4") (pintype "bidirectional"))
    )
    (net (code "70") (name "Net-(TP44-Pad1)") (class "Default")
      (node (ref "TP44") (pin "1") (pinfunction "1_1") (pintype "bidirectional"))
      (node (ref "U8") (pin "5") (pinfunction "5_5") (pintype "bidirectional"))
    )
    (net (code "71") (name "Net-(TP45-Pad1)") (class "Default")
      (node (ref "TP45") (pin "1") (pinfunction "1_1") (pintype "bidirectional"))
      (node (ref "U8") (pin "6") (pinfunction "6_6") (pintype "bidirectional"))
    )
    (net (code "72") (name "Net-(TP46-Pad1)") (class "Default")
      (node (ref "TP46") (pin "1") (pinfunction "1_1") (pintype "bidirectional"))
      (node (ref "U8") (pin "7") (pinfunction "7_7") (pintype "bidirectional"))
    )
    (net (code "73") (name "Net-(TP47-Pad1)") (class "Default")
      (node (ref "TP47") (pin "1") (pinfunction "1_1") (pintype "bidirectional"))
      (node (ref "U8") (pin "8") (pinfunction "8_8") (pintype "bidirectional"))
    )
    (net (code "74") (name "Net-(TP48-Pad1)") (class "Default")
      (node (ref "TP48") (pin "1") (pinfunction "1_1") (pintype "bidirectional"))
      (node (ref "U8") (pin "9") (pinfunction "9_9") (pintype "bidirectional"))
    )
    (net (code "75") (name "Net-(TP49-Pad1)") (class "Default")
      (node (ref "TP49") (pin "1") (pinfunction "1_1") (pintype "bidirectional"))
      (node (ref "U8") (pin "10") (pinfunction "10_10") (pintype "bidirectional"))
    )
    (net (code "76") (name "Net-(TP154-Pad1)") (class "Default")
      (node (ref "TP154") (pin "1") (pinfunction "1_1") (pintype "bidirectional"))
      (node (ref "U9") (pin "1") (pinfunction "1_1") (pintype "bidirectional"))
    )
    (net (code "77") (name "Net-(TP155-Pad1)") (class "Default")
      (node (ref "TP155") (pin "1") (pinfunction "1_1") (pintype "bidirectional"))
      (node (ref "U9") (pin "2") (pinfunction "2_2") (pintype "bidirectional"))
    )
    (net (code "78") (name "Net-(TP156-Pad1)") (class "Default")
      (node (ref "TP156") (pin "1") (pinfunction "1_1") (pintype "bidirectional"))
      (node (ref "U9") (pin "3") (pinfunction "3_3") (pintype "bidirectional"))
    )
    (net (code "79") (name "Net-(TP157-Pad1)") (class "Default")
      (node (ref "TP157") (pin "1") (pinfunction "1_1") (pintype "bidirectional"))
      (node (ref "U9") (pin "4") (pinfunction "4_4") (pintype "bidirectional"))
    )
    (net (code "80") (name "Net-(TP158-Pad1)") (class "Default")
      (node (ref "TP158") (pin "1") (pinfunction "1_1") (pintype "bidirectional"))
      (node (ref "U9") (pin "5") (pinfunction "5_5") (pintype "bidirectional"))
    )
    (net (code "81") (name "Net-(TP159-Pad1)") (class "Default")
      (node (ref "TP159") (pin "1") (pinfunction "1_1") (pintype "bidirectional"))
      (node (ref "U9") (pin "6") (pinfunction "6_6") (pintype "bidirectional"))
    )
    (net (code "82") (name "Net-(TP160-Pad1)") (class "Default")
      (node (ref "TP160") (pin "1") (pinfunction "1_1") (pintype "bidirectional"))
      (node (ref "U9") (pin "7") (pinfunction "7_7") (pintype "bidirectional"))
    )
    (net (code "83") (name "Net-(TP161-Pad1)") (class "Default")
      (node (ref "TP161") (pin "1") (pinfunction "1_1") (pintype "bidirectional"))
      (node (ref "U9") (pin "8") (pinfunction "8_8") (pintype "bidirectional"))
    )
    (net (code "84") (name "Net-(U1A-CAP)") (class "Default")
      (node (ref "C2") (pin "1") (pinfunction "1_1") (pintype "passive"))
      (node (ref "U1") (pin "9") (pinfunction "CAP_9") (pintype "passive"))
    )
    (net (code "85") (name "Net-(U2-Q1)") (class "Default")
      (node (ref "U2") (pin "9") (pinfunction "Q1_9") (pintype "output"))
      (node (ref "U5") (pin "1") (pinfunction "P00_1") (pintype "bidirectional"))
    )
    (net (code "86") (name "Net-(U2-Q2)") (class "Default")
      (node (ref "U2") (pin "7") (pinfunction "Q2_7") (pintype "output"))
      (node (ref "U5") (pin "2") (pinfunction "P01_2") (pintype "bidirectional"))
    )
    (net (code "87") (name "Net-(U2-Q3)") (class "Default")
      (node (ref "U2") (pin "6") (pinfunction "Q3_6") (pintype "output"))
      (node (ref "U5") (pin "3") (pinfunction "P02_3") (pintype "bidirectional"))
    )
    (net (code "88") (name "Net-(U2-Q4)") (class "Default")
      (node (ref "U2") (pin "5") (pinfunction "Q4_5") (pintype "output"))
      (node (ref "U5") (pin "4") (pinfunction "P03_4") (pintype "bidirectional"))
    )
    (net (code "89") (name "Net-(U2-Q5)") (class "Default")
      (node (ref "U2") (pin "3") (pinfunction "Q5_3") (pintype "output"))
      (node (ref "U5") (pin "5") (pinfunction "P04_5") (pintype "bidirectional"))
    )
    (net (code "90") (name "Net-(U2-Q6)") (class "Default")
      (node (ref "U2") (pin "2") (pinfunction "Q6_2") (pintype "output"))
      (node (ref "U5") (pin "6") (pinfunction "P05_6") (pintype "bidirectional"))
    )
    (net (code "91") (name "Net-(U2-Q7)") (class "Default")
      (node (ref "U2") (pin "4") (pinfunction "Q7_4") (pintype "output"))
      (node (ref "U5") (pin "7") (pinfunction "P06_7") (pintype "bidirectional"))
    )
    (net (code "92") (name "Net-(U2-Q8)") (class "Default")
      (node (ref "U2") (pin "13") (pinfunction "Q8_13") (pintype "output"))
      (node (ref "U5") (pin "8") (pinfunction "P07_8") (pintype "bidirectional"))
    )
    (net (code "93") (name "Net-(U2-Q9)") (class "Default")
      (node (ref "U2") (pin "12") (pinfunction "Q9_12") (pintype "output"))
      (node (ref "U5") (pin "10") (pinfunction "P10_10") (pintype "bidirectional"))
    )
    (net (code "94") (name "Net-(U2-Q10)") (class "Default")
      (node (ref "U2") (pin "14") (pinfunction "Q10_14") (pintype "output"))
      (node (ref "U5") (pin "11") (pinfunction "P11_11") (pintype "bidirectional"))
    )
    (net (code "95") (name "Net-(U2-Q11)") (class "Default")
      (node (ref "U2") (pin "15") (pinfunction "Q11_15") (pintype "output"))
      (node (ref "U5") (pin "12") (pinfunction "P12_12") (pintype "bidirectional"))
    )
    (net (code "96") (name "Net-(U2-Q12)") (class "Default")
      (node (ref "U2") (pin "1") (pinfunction "Q12_1") (pintype "output"))
      (node (ref "U5") (pin "13") (pinfunction "P13_13") (pintype "bidirectional"))
    )
    (net (code "97") (name "Net-(U3-Q1)") (class "Default")
      (node (ref "U3") (pin "9") (pinfunction "Q1_9") (pintype "output"))
      (node (ref "U6") (pin "1") (pinfunction "P00_1") (pintype "bidirectional"))
    )
    (net (code "98") (name "Net-(U3-Q2)") (class "Default")
      (node (ref "U3") (pin "7") (pinfunction "Q2_7") (pintype "output"))
      (node (ref "U6") (pin "2") (pinfunction "P01_2") (pintype "bidirectional"))
    )
    (net (code "99") (name "Net-(U3-Q3)") (class "Default")
      (node (ref "U3") (pin "6") (pinfunction "Q3_6") (pintype "output"))
      (node (ref "U6") (pin "3") (pinfunction "P02_3") (pintype "bidirectional"))
    )
    (net (code "100") (name "Net-(U3-Q4)") (class "Default")
      (node (ref "U3") (pin "5") (pinfunction "Q4_5") (pintype "output"))
      (node (ref "U6") (pin "4") (pinfunction "P03_4") (pintype "bidirectional"))
    )
    (net (code "101") (name "Net-(U3-Q5)") (class "Default")
      (node (ref "U3") (pin "3") (pinfunction "Q5_3") (pintype "output"))
      (node (ref "U6") (pin "5") (pinfunction "P04_5") (pintype "bidirectional"))
    )
    (net (code "102") (name "Net-(U3-Q6)") (class "Default")
      (node (ref "U3") (pin "2") (pinfunction "Q6_2") (pintype "output"))
      (node (ref "U6") (pin "6") (pinfunction "P05_6") (pintype "bidirectional"))
    )
    (net (code "103") (name "Net-(U3-Q7)") (class "Default")
      (node (ref "U3") (pin "4") (pinfunction "Q7_4") (pintype "output"))
      (node (ref "U6") (pin "7") (pinfunction "P06_7") (pintype "bidirectional"))
    )
    (net (code "104") (name "Net-(U3-Q8)") (class "Default")
      (node (ref "U3") (pin "13") (pinfunction "Q8_13") (pintype "output"))
      (node (ref "U6") (pin "8") (pinfunction "P07_8") (pintype "bidirectional"))
    )
    (net (code "105") (name "Net-(U3-Q9)") (class "Default")
      (node (ref "U3") (pin "12") (pinfunction "Q9_12") (pintype "output"))
      (node (ref "U6") (pin "10") (pinfunction "P10_10") (pintype "bidirectional"))
    )
    (net (code "106") (name "Net-(U3-Q10)") (class "Default")
      (node (ref "U3") (pin "14") (pinfunction "Q10_14") (pintype "output"))
      (node (ref "U6") (pin "11") (pinfunction "P11_11") (pintype "bidirectional"))
    )
    (net (code "107") (name "Net-(U3-Q11)") (class "Default")
      (node (ref "U3") (pin "15") (pinfunction "Q11_15") (pintype "output"))
      (node (ref "U6") (pin "12") (pinfunction "P12_12") (pintype "bidirectional"))
    )
    (net (code "108") (name "Net-(U3-Q12)") (class "Default")
      (node (ref "U3") (pin "1") (pinfunction "Q12_1") (pintype "output"))
      (node (ref "U6") (pin "13") (pinfunction "P13_13") (pintype "bidirectional"))
    )
    (net (code "109") (name "Net-(U4-FB)") (class "Default")
      (node (ref "C11") (pin "1") (pinfunction "1_1") (pintype "passive"))
      (node (ref "U4") (pin "7") (pinfunction "OUT_7") (pintype "output"))
      (node (ref "U4") (pin "8") (pinfunction "FB_8") (pintype "input"))
      (node (ref "U7") (pin "8") (pinfunction "CH0_8") (pintype "passive"))
    )
    (net (code "110") (name "Net-(U5-P15)") (class "Default")
      (node (ref "TP1") (pin "1") (pinfunction "1_1") (pintype "bidirectional"))
      (node (ref "U5") (pin "15") (pinfunction "P15_15") (pintype "bidirectional"))
    )
    (net (code "111") (name "Net-(U5-P16)") (class "Default")
      (node (ref "TP2") (pin "1") (pinfunction "1_1") (pintype "bidirectional"))
      (node (ref "U5") (pin "16") (pinfunction "P16_16") (pintype "bidirectional"))
    )
    (net (code "112") (name "Net-(U5-P17)") (class "Default")
      (node (ref "TP3") (pin "1") (pinfunction "1_1") (pintype "bidirectional"))
      (node (ref "U5") (pin "17") (pinfunction "P17_17") (pintype "bidirectional"))
    )
    (net (code "113") (name "Net-(U7-ADCINN)") (class "Default")
      (node (ref "U7") (pin "26") (pinfunction "ADCINN_26") (pintype "bidirectional"))
      (node (ref "U7") (pin "27") (pinfunction "MUXOUTN_27") (pintype "bidirectional"))
    )
    (net (code "114") (name "Net-(U7-ADCINP)") (class "Default")
      (node (ref "U7") (pin "24") (pinfunction "MUXOUTP_24") (pintype "bidirectional"))
      (node (ref "U7") (pin "25") (pinfunction "ADCINP_25") (pintype "bidirectional"))
    )
    (net (code "115") (name "Net-(U7-CA0)") (class "Default")
      (node (ref "JP3") (pin "2") (pinfunction "2_2") (pintype "passive"))
      (node (ref "U7") (pin "36") (pinfunction "CA0_36") (pintype "bidirectional"))
    )
    (net (code "116") (name "Net-(U7-CA1)") (class "Default")
      (node (ref "JP4") (pin "2") (pinfunction "2_2") (pintype "passive"))
      (node (ref "U7") (pin "37") (pinfunction "CA1_37") (pintype "bidirectional"))
    )
    (net (code "117") (name "Net-(U8B-1)") (class "Default")
      (node (ref "TP60") (pin "1") (pinfunction "1_1") (pintype "bidirectional"))
      (node (ref "U8") (pin "11") (pinfunction "1_11") (pintype "bidirectional"))
    )
    (net (code "118") (name "Net-(U8B-2)") (class "Default")
      (node (ref "TP61") (pin "1") (pinfunction "1_1") (pintype "bidirectional"))
      (node (ref "U8") (pin "12") (pinfunction "2_12") (pintype "bidirectional"))
    )
    (net (code "119") (name "Net-(U8B-3)") (class "Default")
      (node (ref "TP62") (pin "1") (pinfunction "1_1") (pintype "bidirectional"))
      (node (ref "U8") (pin "13") (pinfunction "3_13") (pintype "bidirectional"))
    )
    (net (code "120") (name "Net-(U8B-4)") (class "Default")
      (node (ref "TP63") (pin "1") (pinfunction "1_1") (pintype "bidirectional"))
      (node (ref "U8") (pin "14") (pinfunction "4_14") (pintype "bidirectional"))
    )
    (net (code "121") (name "Net-(U8B-5)") (class "Default")
      (node (ref "TP64") (pin "1") (pinfunction "1_1") (pintype "bidirectional"))
      (node (ref "U8") (pin "15") (pinfunction "5_15") (pintype "bidirectional"))
    )
    (net (code "122") (name "Net-(U8B-6)") (class "Default")
      (node (ref "TP65") (pin "1") (pinfunction "1_1") (pintype "bidirectional"))
      (node (ref "U8") (pin "16") (pinfunction "6_16") (pintype "bidirectional"))
    )
    (net (code "123") (name "Net-(U8B-7)") (class "Default")
      (node (ref "TP66") (pin "1") (pinfunction "1_1") (pintype "bidirectional"))
      (node (ref "U8") (pin "17") (pinfunction "7_17") (pintype "bidirectional"))
    )
    (net (code "124") (name "Net-(U8B-8)") (class "Default")
      (node (ref "TP67") (pin "1") (pinfunction "1_1") (pintype "bidirectional"))
      (node (ref "U8") (pin "18") (pinfunction "8_18") (pintype "bidirectional"))
    )
    (net (code "125") (name "Net-(U8B-9)") (class "Default")
      (node (ref "TP68") (pin "1") (pinfunction "1_1") (pintype "bidirectional"))
      (node (ref "U8") (pin "19") (pinfunction "9_19") (pintype "bidirectional"))
    )
    (net (code "126") (name "Net-(U8B-10)") (class "Default")
      (node (ref "TP69") (pin "1") (pinfunction "1_1") (pintype "bidirectional"))
      (node (ref "U8") (pin "20") (pinfunction "10_20") (pintype "bidirectional"))
    )
    (net (code "127") (name "Net-(U8C-1)") (class "Default")
      (node (ref "TP94") (pin "1") (pinfunction "1_1") (pintype "bidirectional"))
      (node (ref "U8") (pin "21") (pinfunction "1_21") (pintype "bidirectional"))
    )
    (net (code "128") (name "Net-(U8C-2)") (class "Default")
      (node (ref "TP95") (pin "1") (pinfunction "1_1") (pintype "bidirectional"))
      (node (ref "U8") (pin "22") (pinfunction "2_22") (pintype "bidirectional"))
    )
    (net (code "129") (name "Net-(U8C-3)") (class "Default")
      (node (ref "TP96") (pin "1") (pinfunction "1_1") (pintype "bidirectional"))
      (node (ref "U8") (pin "23") (pinfunction "3_23") (pintype "bidirectional"))
    )
    (net (code "130") (name "Net-(U8C-4)") (class "Default")
      (node (ref "TP97") (pin "1") (pinfunction "1_1") (pintype "bidirectional"))
      (node (ref "U8") (pin "24") (pinfunction "4_24") (pintype "bidirectional"))
    )
    (net (code "131") (name "Net-(U8C-5)") (class "Default")
      (node (ref "TP98") (pin "1") (pinfunction "1_1") (pintype "bidirectional"))
      (node (ref "U8") (pin "25") (pinfunction "5_25") (pintype "bidirectional"))
    )
    (net (code "132") (name "Net-(U8C-6)") (class "Default")
      (node (ref "TP99") (pin "1") (pinfunction "1_1") (pintype "bidirectional"))
      (node (ref "U8") (pin "26") (pinfunction "6_26") (pintype "bidirectional"))
    )
    (net (code "133") (name "Net-(U8C-7)") (class "Default")
      (node (ref "TP100") (pin "1") (pinfunction "1_1") (pintype "bidirectional"))
      (node (ref "U8") (pin "27") (pinfunction "7_27") (pintype "bidirectional"))
    )
    (net (code "134") (name "Net-(U8C-8)") (class "Default")
      (node (ref "TP101") (pin "1") (pinfunction "1_1") (pintype "bidirectional"))
      (node (ref "U8") (pin "28") (pinfunction "8_28") (pintype "bidirectional"))
    )
    (net (code "135") (name "Net-(U8C-9)") (class "Default")
      (node (ref "TP102") (pin "1") (pinfunction "1_1") (pintype "bidirectional"))
      (node (ref "U8") (pin "29") (pinfunction "9_29") (pintype "bidirectional"))
    )
    (net (code "136") (name "Net-(U8C-10)") (class "Default")
      (node (ref "TP103") (pin "1") (pinfunction "1_1") (pintype "bidirectional"))
      (node (ref "U8") (pin "30") (pinfunction "10_30") (pintype "bidirectional"))
    )
    (net (code "137") (name "Net-(U8D-1)") (class "Default")
      (node (ref "TP114") (pin "1") (pinfunction "1_1") (pintype "bidirectional"))
      (node (ref "U8") (pin "31") (pinfunction "1_31") (pintype "bidirectional"))
    )
    (net (code "138") (name "Net-(U8D-2)") (class "Default")
      (node (ref "TP115") (pin "1") (pinfunction "1_1") (pintype "bidirectional"))
      (node (ref "U8") (pin "32") (pinfunction "2_32") (pintype "bidirectional"))
    )
    (net (code "139") (name "Net-(U8D-3)") (class "Default")
      (node (ref "TP116") (pin "1") (pinfunction "1_1") (pintype "bidirectional"))
      (node (ref "U8") (pin "33") (pinfunction "3_33") (pintype "bidirectional"))
    )
    (net (code "140") (name "Net-(U8D-4)") (class "Default")
      (node (ref "TP117") (pin "1") (pinfunction "1_1") (pintype "bidirectional"))
      (node (ref "U8") (pin "34") (pinfunction "4_34") (pintype "bidirectional"))
    )
    (net (code "141") (name "Net-(U8D-5)") (class "Default")
      (node (ref "TP118") (pin "1") (pinfunction "1_1") (pintype "bidirectional"))
      (node (ref "U8") (pin "35") (pinfunction "5_35") (pintype "bidirectional"))
    )
    (net (code "142") (name "Net-(U8D-6)") (class "Default")
      (node (ref "TP119") (pin "1") (pinfunction "1_1") (pintype "bidirectional"))
      (node (ref "U8") (pin "36") (pinfunction "6_36") (pintype "bidirectional"))
    )
    (net (code "143") (name "Net-(U8D-7)") (class "Default")
      (node (ref "TP120") (pin "1") (pinfunction "1_1") (pintype "bidirectional"))
      (node (ref "U8") (pin "37") (pinfunction "7_37") (pintype "bidirectional"))
    )
    (net (code "144") (name "Net-(U8D-8)") (class "Default")
      (node (ref "TP121") (pin "1") (pinfunction "1_1") (pintype "bidirectional"))
      (node (ref "U8") (pin "38") (pinfunction "8_38") (pintype "bidirectional"))
    )
    (net (code "145") (name "Net-(U8D-9)") (class "Default")
      (node (ref "TP122") (pin "1") (pinfunction "1_1") (pintype "bidirectional"))
      (node (ref "U8") (pin "39") (pinfunction "9_39") (pintype "bidirectional"))
    )
    (net (code "146") (name "Net-(U8D-10)") (class "Default")
      (node (ref "TP123") (pin "1") (pinfunction "1_1") (pintype "bidirectional"))
      (node (ref "U8") (pin "40") (pinfunction "10_40") (pintype "bidirectional"))
    )
    (net (code "147") (name "Net-(U8E-1)") (class "Default")
      (node (ref "TP134") (pin "1") (pinfunction "1_1") (pintype "bidirectional"))
      (node (ref "U8") (pin "41") (pinfunction "1_41") (pintype "bidirectional"))
    )
    (net (code "148") (name "Net-(U8E-2)") (class "Default")
      (node (ref "TP135") (pin "1") (pinfunction "1_1") (pintype "bidirectional"))
      (node (ref "U8") (pin "42") (pinfunction "2_42") (pintype "bidirectional"))
    )
    (net (code "149") (name "Net-(U8E-3)") (class "Default")
      (node (ref "TP136") (pin "1") (pinfunction "1_1") (pintype "bidirectional"))
      (node (ref "U8") (pin "43") (pinfunction "3_43") (pintype "bidirectional"))
    )
    (net (code "150") (name "Net-(U8E-4)") (class "Default")
      (node (ref "TP137") (pin "1") (pinfunction "1_1") (pintype "bidirectional"))
      (node (ref "U8") (pin "44") (pinfunction "4_44") (pintype "bidirectional"))
    )
    (net (code "151") (name "Net-(U8E-5)") (class "Default")
      (node (ref "TP138") (pin "1") (pinfunction "1_1") (pintype "bidirectional"))
      (node (ref "U8") (pin "45") (pinfunction "5_45") (pintype "bidirectional"))
    )
    (net (code "152") (name "Net-(U8E-6)") (class "Default")
      (node (ref "TP139") (pin "1") (pinfunction "1_1") (pintype "bidirectional"))
      (node (ref "U8") (pin "46") (pinfunction "6_46") (pintype "bidirectional"))
    )
    (net (code "153") (name "Net-(U8E-7)") (class "Default")
      (node (ref "TP140") (pin "1") (pinfunction "1_1") (pintype "bidirectional"))
      (node (ref "U8") (pin "47") (pinfunction "7_47") (pintype "bidirectional"))
    )
    (net (code "154") (name "Net-(U8E-8)") (class "Default")
      (node (ref "TP141") (pin "1") (pinfunction "1_1") (pintype "bidirectional"))
      (node (ref "U8") (pin "48") (pinfunction "8_48") (pintype "bidirectional"))
    )
    (net (code "155") (name "Net-(U8E-9)") (class "Default")
      (node (ref "TP142") (pin "1") (pinfunction "1_1") (pintype "bidirectional"))
      (node (ref "U8") (pin "49") (pinfunction "9_49") (pintype "bidirectional"))
    )
    (net (code "156") (name "Net-(U8E-10)") (class "Default")
      (node (ref "TP143") (pin "1") (pinfunction "1_1") (pintype "bidirectional"))
      (node (ref "U8") (pin "50") (pinfunction "10_50") (pintype "bidirectional"))
    )
    (net (code "157") (name "Net-(U8F-1)") (class "Default")
      (node (ref "TP50") (pin "1") (pinfunction "1_1") (pintype "bidirectional"))
      (node (ref "U8") (pin "51") (pinfunction "1_51") (pintype "bidirectional"))
    )
    (net (code "158") (name "Net-(U8F-2)") (class "Default")
      (node (ref "TP51") (pin "1") (pinfunction "1_1") (pintype "bidirectional"))
      (node (ref "U8") (pin "52") (pinfunction "2_52") (pintype "bidirectional"))
    )
    (net (code "159") (name "Net-(U8F-3)") (class "Default")
      (node (ref "TP52") (pin "1") (pinfunction "1_1") (pintype "bidirectional"))
      (node (ref "U8") (pin "53") (pinfunction "3_53") (pintype "bidirectional"))
    )
    (net (code "160") (name "Net-(U8F-4)") (class "Default")
      (node (ref "TP53") (pin "1") (pinfunction "1_1") (pintype "bidirectional"))
      (node (ref "U8") (pin "54") (pinfunction "4_54") (pintype "bidirectional"))
    )
    (net (code "161") (name "Net-(U8F-5)") (class "Default")
      (node (ref "TP54") (pin "1") (pinfunction "1_1") (pintype "bidirectional"))
      (node (ref "U8") (pin "55") (pinfunction "5_55") (pintype "bidirectional"))
    )
    (net (code "162") (name "Net-(U8F-6)") (class "Default")
      (node (ref "TP55") (pin "1") (pinfunction "1_1") (pintype "bidirectional"))
      (node (ref "U8") (pin "56") (pinfunction "6_56") (pintype "bidirectional"))
    )
    (net (code "163") (name "Net-(U8F-7)") (class "Default")
      (node (ref "TP56") (pin "1") (pinfunction "1_1") (pintype "bidirectional"))
      (node (ref "U8") (pin "57") (pinfunction "7_57") (pintype "bidirectional"))
    )
    (net (code "164") (name "Net-(U8F-8)") (class "Default")
      (node (ref "TP57") (pin "1") (pinfunction "1_1") (pintype "bidirectional"))
      (node (ref "U8") (pin "58") (pinfunction "8_58") (pintype "bidirectional"))
    )
    (net (code "165") (name "Net-(U8F-9)") (class "Default")
      (node (ref "TP58") (pin "1") (pinfunction "1_1") (pintype "bidirectional"))
      (node (ref "U8") (pin "59") (pinfunction "9_59") (pintype "bidirectional"))
    )
    (net (code "166") (name "Net-(U8F-10)") (class "Default")
      (node (ref "TP59") (pin "1") (pinfunction "1_1") (pintype "bidirectional"))
      (node (ref "U8") (pin "60") (pinfunction "10_60") (pintype "bidirectional"))
    )
    (net (code "167") (name "Net-(U8G-1)") (class "Default")
      (node (ref "TP70") (pin "1") (pinfunction "1_1") (pintype "bidirectional"))
      (node (ref "U8") (pin "61") (pinfunction "1_61") (pintype "bidirectional"))
    )
    (net (code "168") (name "Net-(U8G-2)") (class "Default")
      (node (ref "TP71") (pin "1") (pinfunction "1_1") (pintype "bidirectional"))
      (node (ref "U8") (pin "62") (pinfunction "2_62") (pintype "bidirectional"))
    )
    (net (code "169") (name "Net-(U8G-3)") (class "Default")
      (node (ref "TP72") (pin "1") (pinfunction "1_1") (pintype "bidirectional"))
      (node (ref "U8") (pin "63") (pinfunction "3_63") (pintype "bidirectional"))
    )
    (net (code "170") (name "Net-(U8G-4)") (class "Default")
      (node (ref "TP73") (pin "1") (pinfunction "1_1") (pintype "bidirectional"))
      (node (ref "U8") (pin "64") (pinfunction "4_64") (pintype "bidirectional"))
    )
    (net (code "171") (name "Net-(U8G-5)") (class "Default")
      (node (ref "TP74") (pin "1") (pinfunction "1_1") (pintype "bidirectional"))
      (node (ref "U8") (pin "65") (pinfunction "5_65") (pintype "bidirectional"))
    )
    (net (code "172") (name "Net-(U8G-6)") (class "Default")
      (node (ref "TP75") (pin "1") (pinfunction "1_1") (pintype "bidirectional"))
      (node (ref "U8") (pin "66") (pinfunction "6_66") (pintype "bidirectional"))
    )
    (net (code "173") (name "Net-(U8G-7)") (class "Default")
      (node (ref "TP76") (pin "1") (pinfunction "1_1") (pintype "bidirectional"))
      (node (ref "U8") (pin "67") (pinfunction "7_67") (pintype "bidirectional"))
    )
    (net (code "174") (name "Net-(U8G-8)") (class "Default")
      (node (ref "TP77") (pin "1") (pinfunction "1_1") (pintype "bidirectional"))
      (node (ref "U8") (pin "68") (pinfunction "8_68") (pintype "bidirectional"))
    )
    (net (code "175") (name "Net-(U8G-9)") (class "Default")
      (node (ref "TP78") (pin "1") (pinfunction "1_1") (pintype "bidirectional"))
      (node (ref "U8") (pin "69") (pinfunction "9_69") (pintype "bidirectional"))
    )
    (net (code "176") (name "Net-(U8G-10)") (class "Default")
      (node (ref "TP79") (pin "1") (pinfunction "1_1") (pintype "bidirectional"))
      (node (ref "U8") (pin "70") (pinfunction "10_70") (pintype "bidirectional"))
    )
    (net (code "177") (name "Net-(U8H-1)") (class "Default")
      (node (ref "TP104") (pin "1") (pinfunction "1_1") (pintype "bidirectional"))
      (node (ref "U8") (pin "71") (pinfunction "1_71") (pintype "bidirectional"))
    )
    (net (code "178") (name "Net-(U8H-2)") (class "Default")
      (node (ref "TP105") (pin "1") (pinfunction "1_1") (pintype "bidirectional"))
      (node (ref "U8") (pin "72") (pinfunction "2_72") (pintype "bidirectional"))
    )
    (net (code "179") (name "Net-(U8H-3)") (class "Default")
      (node (ref "TP106") (pin "1") (pinfunction "1_1") (pintype "bidirectional"))
      (node (ref "U8") (pin "73") (pinfunction "3_73") (pintype "bidirectional"))
    )
    (net (code "180") (name "Net-(U8H-4)") (class "Default")
      (node (ref "TP107") (pin "1") (pinfunction "1_1") (pintype "bidirectional"))
      (node (ref "U8") (pin "74") (pinfunction "4_74") (pintype "bidirectional"))
    )
    (net (code "181") (name "Net-(U8H-5)") (class "Default")
      (node (ref "TP108") (pin "1") (pinfunction "1_1") (pintype "bidirectional"))
      (node (ref "U8") (pin "75") (pinfunction "5_75") (pintype "bidirectional"))
    )
    (net (code "182") (name "Net-(U8H-6)") (class "Default")
      (node (ref "TP109") (pin "1") (pinfunction "1_1") (pintype "bidirectional"))
      (node (ref "U8") (pin "76") (pinfunction "6_76") (pintype "bidirectional"))
    )
    (net (code "183") (name "Net-(U8H-7)") (class "Default")
      (node (ref "TP110") (pin "1") (pinfunction "1_1") (pintype "bidirectional"))
      (node (ref "U8") (pin "77") (pinfunction "7_77") (pintype "bidirectional"))
    )
    (net (code "184") (name "Net-(U8H-8)") (class "Default")
      (node (ref "TP111") (pin "1") (pinfunction "1_1") (pintype "bidirectional"))
      (node (ref "U8") (pin "78") (pinfunction "8_78") (pintype "bidirectional"))
    )
    (net (code "185") (name "Net-(U8H-9)") (class "Default")
      (node (ref "TP112") (pin "1") (pinfunction "1_1") (pintype "bidirectional"))
      (node (ref "U8") (pin "79") (pinfunction "9_79") (pintype "bidirectional"))
    )
    (net (code "186") (name "Net-(U8H-10)") (class "Default")
      (node (ref "TP113") (pin "1") (pinfunction "1_1") (pintype "bidirectional"))
      (node (ref "U8") (pin "80") (pinfunction "10_80") (pintype "bidirectional"))
    )
    (net (code "187") (name "Net-(U8I-1)") (class "Default")
      (node (ref "TP124") (pin "1") (pinfunction "1_1") (pintype "bidirectional"))
      (node (ref "U8") (pin "81") (pinfunction "1_81") (pintype "bidirectional"))
    )
    (net (code "188") (name "Net-(U8I-2)") (class "Default")
      (node (ref "TP125") (pin "1") (pinfunction "1_1") (pintype "bidirectional"))
      (node (ref "U8") (pin "82") (pinfunction "2_82") (pintype "bidirectional"))
    )
    (net (code "189") (name "Net-(U8I-3)") (class "Default")
      (node (ref "TP126") (pin "1") (pinfunction "1_1") (pintype "bidirectional"))
      (node (ref "U8") (pin "83") (pinfunction "3_83") (pintype "bidirectional"))
    )
    (net (code "190") (name "Net-(U8I-4)") (class "Default")
      (node (ref "TP127") (pin "1") (pinfunction "1_1") (pintype "bidirectional"))
      (node (ref "U8") (pin "84") (pinfunction "4_84") (pintype "bidirectional"))
    )
    (net (code "191") (name "Net-(U8I-5)") (class "Default")
      (node (ref "TP128") (pin "1") (pinfunction "1_1") (pintype "bidirectional"))
      (node (ref "U8") (pin "85") (pinfunction "5_85") (pintype "bidirectional"))
    )
    (net (code "192") (name "Net-(U8I-6)") (class "Default")
      (node (ref "TP129") (pin "1") (pinfunction "1_1") (pintype "bidirectional"))
      (node (ref "U8") (pin "86") (pinfunction "6_86") (pintype "bidirectional"))
    )
    (net (code "193") (name "Net-(U8I-7)") (class "Default")
      (node (ref "TP130") (pin "1") (pinfunction "1_1") (pintype "bidirectional"))
      (node (ref "U8") (pin "87") (pinfunction "7_87") (pintype "bidirectional"))
    )
    (net (code "194") (name "Net-(U8I-8)") (class "Default")
      (node (ref "TP131") (pin "1") (pinfunction "1_1") (pintype "bidirectional"))
      (node (ref "U8") (pin "88") (pinfunction "8_88") (pintype "bidirectional"))
    )
    (net (code "195") (name "Net-(U8I-9)") (class "Default")
      (node (ref "TP132") (pin "1") (pinfunction "1_1") (pintype "bidirectional"))
      (node (ref "U8") (pin "89") (pinfunction "9_89") (pintype "bidirectional"))
    )
    (net (code "196") (name "Net-(U8I-10)") (class "Default")
      (node (ref "TP133") (pin "1") (pinfunction "1_1") (pintype "bidirectional"))
      (node (ref "U8") (pin "90") (pinfunction "10_90") (pintype "bidirectional"))
    )
    (net (code "197") (name "Net-(U8J-1)") (class "Default")
      (node (ref "TP144") (pin "1") (pinfunction "1_1") (pintype "bidirectional"))
      (node (ref "U8") (pin "91") (pinfunction "1_91") (pintype "bidirectional"))
    )
    (net (code "198") (name "Net-(U8J-2)") (class "Default")
      (node (ref "TP145") (pin "1") (pinfunction "1_1") (pintype "bidirectional"))
      (node (ref "U8") (pin "92") (pinfunction "2_92") (pintype "bidirectional"))
    )
    (net (code "199") (name "Net-(U8J-3)") (class "Default")
      (node (ref "TP146") (pin "1") (pinfunction "1_1") (pintype "bidirectional"))
      (node (ref "U8") (pin "93") (pinfunction "3_93") (pintype "bidirectional"))
    )
    (net (code "200") (name "Net-(U8J-4)") (class "Default")
      (node (ref "TP147") (pin "1") (pinfunction "1_1") (pintype "bidirectional"))
      (node (ref "U8") (pin "94") (pinfunction "4_94") (pintype "bidirectional"))
    )
    (net (code "201") (name "Net-(U8J-5)") (class "Default")
      (node (ref "TP148") (pin "1") (pinfunction "1_1") (pintype "bidirectional"))
      (node (ref "U8") (pin "95") (pinfunction "5_95") (pintype "bidirectional"))
    )
    (net (code "202") (name "Net-(U8J-6)") (class "Default")
      (node (ref "TP149") (pin "1") (pinfunction "1_1") (pintype "bidirectional"))
      (node (ref "U8") (pin "96") (pinfunction "6_96") (pintype "bidirectional"))
    )
    (net (code "203") (name "Net-(U8J-7)") (class "Default")
      (node (ref "TP150") (pin "1") (pinfunction "1_1") (pintype "bidirectional"))
      (node (ref "U8") (pin "97") (pinfunction "7_97") (pintype "bidirectional"))
    )
    (net (code "204") (name "Net-(U8J-8)") (class "Default")
      (node (ref "TP151") (pin "1") (pinfunction "1_1") (pintype "bidirectional"))
      (node (ref "U8") (pin "98") (pinfunction "8_98") (pintype "bidirectional"))
    )
    (net (code "205") (name "Net-(U8J-9)") (class "Default")
      (node (ref "TP152") (pin "1") (pinfunction "1_1") (pintype "bidirectional"))
      (node (ref "U8") (pin "99") (pinfunction "9_99") (pintype "bidirectional"))
    )
    (net (code "206") (name "Net-(U8J-10)") (class "Default")
      (node (ref "TP153") (pin "1") (pinfunction "1_1") (pintype "bidirectional"))
      (node (ref "U8") (pin "100") (pinfunction "10_100") (pintype "bidirectional"))
    )
    (net (code "207") (name "Net-(U9B-1)") (class "Default")
      (node (ref "TP170") (pin "1") (pinfunction "1_1") (pintype "bidirectional"))
      (node (ref "U9") (pin "9") (pinfunction "1_9") (pintype "bidirectional"))
    )
    (net (code "208") (name "Net-(U9B-2)") (class "Default")
      (node (ref "TP171") (pin "1") (pinfunction "1_1") (pintype "bidirectional"))
      (node (ref "U9") (pin "10") (pinfunction "2_10") (pintype "bidirectional"))
    )
    (net (code "209") (name "Net-(U9B-3)") (class "Default")
      (node (ref "TP172") (pin "1") (pinfunction "1_1") (pintype "bidirectional"))
      (node (ref "U9") (pin "11") (pinfunction "3_11") (pintype "bidirectional"))
    )
    (net (code "210") (name "Net-(U9B-4)") (class "Default")
      (node (ref "TP173") (pin "1") (pinfunction "1_1") (pintype "bidirectional"))
      (node (ref "U9") (pin "12") (pinfunction "4_12") (pintype "bidirectional"))
    )
    (net (code "211") (name "Net-(U9B-5)") (class "Default")
      (node (ref "TP174") (pin "1") (pinfunction "1_1") (pintype "bidirectional"))
      (node (ref "U9") (pin "13") (pinfunction "5_13") (pintype "bidirectional"))
    )
    (net (code "212") (name "Net-(U9B-6)") (class "Default")
      (node (ref "TP175") (pin "1") (pinfunction "1_1") (pintype "bidirectional"))
      (node (ref "U9") (pin "14") (pinfunction "6_14") (pintype "bidirectional"))
    )
    (net (code "213") (name "Net-(U9B-7)") (class "Default")
      (node (ref "TP176") (pin "1") (pinfunction "1_1") (pintype "bidirectional"))
      (node (ref "U9") (pin "15") (pinfunction "7_15") (pintype "bidirectional"))
    )
    (net (code "214") (name "Net-(U9B-8)") (class "Default")
      (node (ref "TP177") (pin "1") (pinfunction "1_1") (pintype "bidirectional"))
      (node (ref "U9") (pin "16") (pinfunction "8_16") (pintype "bidirectional"))
    )
    (net (code "215") (name "Net-(U9C-1)") (class "Default")
      (node (ref "TP162") (pin "1") (pinfunction "1_1") (pintype "bidirectional"))
      (node (ref "U9") (pin "17") (pinfunction "1_17") (pintype "bidirectional"))
    )
    (net (code "216") (name "Net-(U9C-2)") (class "Default")
      (node (ref "TP163") (pin "1") (pinfunction "1_1") (pintype "bidirectional"))
      (node (ref "U9") (pin "18") (pinfunction "2_18") (pintype "bidirectional"))
    )
    (net (code "217") (name "Net-(U9C-3)") (class "Default")
      (node (ref "TP164") (pin "1") (pinfunction "1_1") (pintype "bidirectional"))
      (node (ref "U9") (pin "19") (pinfunction "3_19") (pintype "bidirectional"))
    )
    (net (code "218") (name "Net-(U9C-4)") (class "Default")
      (node (ref "TP165") (pin "1") (pinfunction "1_1") (pintype "bidirectional"))
      (node (ref "U9") (pin "20") (pinfunction "4_20") (pintype "bidirectional"))
    )
    (net (code "219") (name "Net-(U9C-5)") (class "Default")
      (node (ref "TP166") (pin "1") (pinfunction "1_1") (pintype "bidirectional"))
      (node (ref "U9") (pin "21") (pinfunction "5_21") (pintype "bidirectional"))
    )
    (net (code "220") (name "Net-(U9C-6)") (class "Default")
      (node (ref "TP167") (pin "1") (pinfunction "1_1") (pintype "bidirectional"))
      (node (ref "U9") (pin "22") (pinfunction "6_22") (pintype "bidirectional"))
    )
    (net (code "221") (name "Net-(U9C-7)") (class "Default")
      (node (ref "TP168") (pin "1") (pinfunction "1_1") (pintype "bidirectional"))
      (node (ref "U9") (pin "23") (pinfunction "7_23") (pintype "bidirectional"))
    )
    (net (code "222") (name "Net-(U9C-8)") (class "Default")
      (node (ref "TP169") (pin "1") (pinfunction "1_1") (pintype "bidirectional"))
      (node (ref "U9") (pin "24") (pinfunction "8_24") (pintype "bidirectional"))
    )
    (net (code "223") (name "Net-(U9D-1)") (class "Default")
      (node (ref "TP178") (pin "1") (pinfunction "1_1") (pintype "bidirectional"))
      (node (ref "U9") (pin "25") (pinfunction "1_25") (pintype "bidirectional"))
    )
    (net (code "224") (name "Net-(U9D-2)") (class "Default")
      (node (ref "TP179") (pin "1") (pinfunction "1_1") (pintype "bidirectional"))
      (node (ref "U9") (pin "26") (pinfunction "2_26") (pintype "bidirectional"))
    )
    (net (code "225") (name "Net-(U9D-3)") (class "Default")
      (node (ref "TP180") (pin "1") (pinfunction "1_1") (pintype "bidirectional"))
      (node (ref "U9") (pin "27") (pinfunction "3_27") (pintype "bidirectional"))
    )
    (net (code "226") (name "Net-(U9D-4)") (class "Default")
      (node (ref "TP181") (pin "1") (pinfunction "1_1") (pintype "bidirectional"))
      (node (ref "U9") (pin "28") (pinfunction "4_28") (pintype "bidirectional"))
    )
    (net (code "227") (name "Net-(U9D-5)") (class "Default")
      (node (ref "TP182") (pin "1") (pinfunction "1_1") (pintype "bidirectional"))
      (node (ref "U9") (pin "29") (pinfunction "5_29") (pintype "bidirectional"))
    )
    (net (code "228") (name "Net-(U9D-6)") (class "Default")
      (node (ref "TP183") (pin "1") (pinfunction "1_1") (pintype "bidirectional"))
      (node (ref "U9") (pin "30") (pinfunction "6_30") (pintype "bidirectional"))
    )
    (net (code "229") (name "Net-(U9D-7)") (class "Default")
      (node (ref "TP184") (pin "1") (pinfunction "1_1") (pintype "bidirectional"))
      (node (ref "U9") (pin "31") (pinfunction "7_31") (pintype "bidirectional"))
    )
    (net (code "230") (name "Net-(U9D-8)") (class "Default")
      (node (ref "TP185") (pin "1") (pinfunction "1_1") (pintype "bidirectional"))
      (node (ref "U9") (pin "32") (pinfunction "8_32") (pintype "bidirectional"))
    )
    (net (code "231") (name "PGND") (class "Default")
      (node (ref "C1") (pin "2") (pinfunction "2_2") (pintype "passive"))
      (node (ref "J1") (pin "6") (pinfunction "6_6") (pintype "bidirectional"))
      (node (ref "J2") (pin "2") (pinfunction "2_2") (pintype "bidirectional"))
      (node (ref "J2") (pin "4") (pinfunction "4_4") (pintype "bidirectional"))
      (node (ref "J8") (pin "1") (pinfunction "PGND_1") (pintype "power_in"))
      (node (ref "J8") (pin "100") (pinfunction "PGND_100") (pintype "power_in"))
      (node (ref "J8") (pin "102") (pinfunction "PGND_102") (pintype "power_in"))
      (node (ref "J8") (pin "104") (pinfunction "PGND_104") (pintype "power_in"))
      (node (ref "J8") (pin "106") (pinfunction "PGND_106") (pintype "power_in"))
      (node (ref "J8") (pin "108") (pinfunction "PGND_108") (pintype "power_in"))
      (node (ref "J8") (pin "11") (pinfunction "PGND_11") (pintype "power_in"))
      (node (ref "J8") (pin "110") (pinfunction "PGND_110") (pintype "power_in"))
      (node (ref "J8") (pin "112") (pinfunction "PGND_112") (pintype "power_in"))
      (node (ref "J8") (pin "114") (pinfunction "PGND_114") (pintype "power_in"))
      (node (ref "J8") (pin "116") (pinfunction "PGND_116") (pintype "power_in"))
      (node (ref "J8") (pin "118") (pinfunction "PGND_118") (pintype "power_in"))
      (node (ref "J8") (pin "120") (pinfunction "PGND_120") (pintype "power_in"))
      (node (ref "J8") (pin "122") (pinfunction "PGND_122") (pintype "power_in"))
      (node (ref "J8") (pin "124") (pinfunction "PGND_124") (pintype "power_in"))
      (node (ref "J8") (pin "126") (pinfunction "PGND_126") (pintype "power_in"))
      (node (ref "J8") (pin "128") (pinfunction "PGND_128") (pintype "power_in"))
      (node (ref "J8") (pin "13") (pinfunction "PGND_13") (pintype "power_in"))
      (node (ref "J8") (pin "130") (pinfunction "PGND_130") (pintype "power_in"))
      (node (ref "J8") (pin "131") (pinfunction "PGND_131") (pintype "power_in"))
      (node (ref "J8") (pin "132") (pinfunction "PGND_132") (pintype "power_in"))
      (node (ref "J8") (pin "133") (pinfunction "PGND_133") (pintype "power_in"))
      (node (ref "J8") (pin "134") (pinfunction "PGND_134") (pintype "power_in"))
      (node (ref "J8") (pin "135") (pinfunction "PGND_135") (pintype "power_in"))
      (node (ref "J8") (pin "136") (pinfunction "PGND_136") (pintype "power_in"))
      (node (ref "J8") (pin "137") (pinfunction "PGND_137") (pintype "power_in"))
      (node (ref "J8") (pin "138") (pinfunction "PGND_138") (pintype "power_in"))
      (node (ref "J8") (pin "139") (pinfunction "PGND_139") (pintype "power_in"))
      (node (ref "J8") (pin "140") (pinfunction "PGND_140") (pintype "power_in"))
      (node (ref "J8") (pin "15") (pinfunction "PGND_15") (pintype "power_in"))
      (node (ref "J8") (pin "17") (pinfunction "PGND_17") (pintype "power_in"))
      (node (ref "J8") (pin "19") (pinfunction "PGND_19") (pintype "power_in"))
      (node (ref "J8") (pin "3") (pinfunction "PGND_3") (pintype "power_in"))
      (node (ref "J8") (pin "41") (pinfunction "PGND_41") (pintype "power_in"))
      (node (ref "J8") (pin "43") (pinfunction "PGND_43") (pintype "power_in"))
      (node (ref "J8") (pin "45") (pinfunction "PGND_45") (pintype "power_in"))
      (node (ref "J8") (pin "47") (pinfunction "PGND_47") (pintype "power_in"))
      (node (ref "J8") (pin "49") (pinfunction "PGND_49") (pintype "power_in"))
      (node (ref "J8") (pin "5") (pinfunction "PGND_5") (pintype "power_in"))
      (node (ref "J8") (pin "51") (pinfunction "PGND_51") (pintype "power_in"))
      (node (ref "J8") (pin "53") (pinfunction "PGND_53") (pintype "power_in"))
      (node (ref "J8") (pin "55") (pinfunction "PGND_55") (pintype "power_in"))
      (node (ref "J8") (pin "57") (pinfunction "PGND_57") (pintype "power_in"))
      (node (ref "J8") (pin "59") (pinfunction "PGND_59") (pintype "power_in"))
      (node (ref "J8") (pin "61") (pinfunction "PGND_61") (pintype "power_in"))
      (node (ref "J8") (pin "63") (pinfunction "PGND_63") (pintype "power_in"))
      (node (ref "J8") (pin "65") (pinfunction "PGND_65") (pintype "power_in"))
      (node (ref "J8") (pin "67") (pinfunction "PGND_67") (pintype "power_in"))
      (node (ref "J8") (pin "69") (pinfunction "PGND_69") (pintype "power_in"))
      (node (ref "J8") (pin "7") (pinfunction "PGND_7") (pintype "power_in"))
      (node (ref "J8") (pin "82") (pinfunction "PGND_82") (pintype "power_in"))
      (node (ref "J8") (pin "84") (pinfunction "PGND_84") (pintype "power_in"))
      (node (ref "J8") (pin "86") (pinfunction "PGND_86") (pintype "power_in"))
      (node (ref "J8") (pin "88") (pinfunction "PGND_88") (pintype "power_in"))
      (node (ref "J8") (pin "9") (pinfunction "PGND_9") (pintype "power_in"))
      (node (ref "J8") (pin "90") (pinfunction "PGND_90") (pintype "power_in"))
      (node (ref "J8") (pin "92") (pinfunction "PGND_92") (pintype "power_in"))
      (node (ref "J8") (pin "94") (pinfunction "PGND_94") (pintype "power_in"))
      (node (ref "J8") (pin "96") (pinfunction "PGND_96") (pintype "power_in"))
      (node (ref "J8") (pin "98") (pinfunction "PGND_98") (pintype "power_in"))
      (node (ref "JP2") (pin "2") (pinfunction "2_2") (pintype "passive"))
      (node (ref "TP82") (pin "1") (pinfunction "1_1") (pintype "bidirectional"))
      (node (ref "TP83") (pin "1") (pinfunction "1_1") (pintype "bidirectional"))
      (node (ref "TP84") (pin "1") (pinfunction "1_1") (pintype "bidirectional"))
      (node (ref "TP85") (pin "1") (pinfunction "1_1") (pintype "bidirectional"))
    )
    (net (code "232") (name "unconnected-(J8B-GPIO_163-Pad163)") (class "Default")
      (node (ref "J8") (pin "163") (pinfunction "GPIO_163_163") (pintype "bidirectional"))
    )
    (net (code "233") (name "unconnected-(J8B-GPIO_165-Pad165)") (class "Default")
      (node (ref "J8") (pin "165") (pinfunction "GPIO_165_165") (pintype "bidirectional"))
    )
    (net (code "234") (name "unconnected-(J8B-GPIO_167-Pad167)") (class "Default")
      (node (ref "J8") (pin "167") (pinfunction "GPIO_167_167") (pintype "bidirectional"))
    )
    (net (code "235") (name "unconnected-(U1A-INT1-Pad13)") (class "Default")
      (node (ref "U1") (pin "13") (pinfunction "INT1_13") (pintype "bidirectional"))
    )
    (net (code "236") (name "unconnected-(U1A-INT2-Pad1)") (class "Default")
      (node (ref "U1") (pin "1") (pinfunction "INT2_1") (pintype "bidirectional"))
    )
    (net (code "237") (name "unconnected-(U1B-PA00-Pad27)") (class "Default")
      (node (ref "U1") (pin "27") (pinfunction "PA00_27") (pintype "bidirectional"))
    )
    (net (code "238") (name "unconnected-(U1B-PA01-Pad26)") (class "Default")
      (node (ref "U1") (pin "26") (pinfunction "PA01_26") (pintype "bidirectional"))
    )
    (net (code "239") (name "unconnected-(U1B-PA20-Pad18)") (class "Default")
      (node (ref "U1") (pin "18") (pinfunction "PA20_18") (pintype "bidirectional"))
    )
    (net (code "240") (name "unconnected-(U1B-PA21-Pad17)") (class "Default")
      (node (ref "U1") (pin "17") (pinfunction "PA21_17") (pintype "bidirectional"))
    )
    (net (code "241") (name "unconnected-(U1B-PA22-Pad16)") (class "Default")
      (node (ref "U1") (pin "16") (pinfunction "PA22_16") (pintype "bidirectional"))
    )
    (net (code "242") (name "unconnected-(U1B-PA23-Pad15)") (class "Default")
      (node (ref "U1") (pin "15") (pinfunction "PA23_15") (pintype "bidirectional"))
    )
    (net (code "243") (name "unconnected-(U1B-PA24-Pad14)") (class "Default")
      (node (ref "U1") (pin "14") (pinfunction "PA24_14") (pintype "bidirectional"))
    )
    (net (code "244") (name "unconnected-(U1B-PA28-Pad10)") (class "Default")
      (node (ref "U1") (pin "10") (pinfunction "PA28_10") (pintype "bidirectional"))
    )
    (net (code "245") (name "unconnected-(U1B-PA30-Pad8)") (class "Default")
      (node (ref "U1") (pin "8") (pinfunction "PA30_8") (pintype "bidirectional"))
    )
    (net (code "246") (name "unconnected-(U1B-PA31-Pad7)") (class "Default")
      (node (ref "U1") (pin "7") (pinfunction "PA31_7") (pintype "bidirectional"))
    )
    (net (code "247") (name "unconnected-(U1B-PB00-Pad6)") (class "Default")
      (node (ref "U1") (pin "6") (pinfunction "PB00_6") (pintype "bidirectional"))
    )
    (net (code "248") (name "unconnected-(U1B-PB01-Pad5)") (class "Default")
      (node (ref "U1") (pin "5") (pinfunction "PB01_5") (pintype "bidirectional"))
    )
    (net (code "249") (name "unconnected-(U1B-PB02-Pad4)") (class "Default")
      (node (ref "U1") (pin "4") (pinfunction "PB02_4") (pintype "bidirectional"))
    )
    (net (code "250") (name "unconnected-(U1B-PB16-Pad20)") (class "Default")
      (node (ref "U1") (pin "20") (pinfunction "PB16_20") (pintype "bidirectional"))
    )
    (net (code "251") (name "unconnected-(U1B-PB17-Pad19)") (class "Default")
      (node (ref "U1") (pin "19") (pinfunction "PB17_19") (pintype "bidirectional"))
    )
    (net (code "252") (name "unconnected-(U5-~{INT}-Pad22)") (class "Default")
      (node (ref "U5") (pin "22") (pinfunction "~{INT}_22") (pintype "output"))
    )
    (net (code "253") (name "unconnected-(U6-~{INT}-Pad22)") (class "Default")
      (node (ref "U6") (pin "22") (pinfunction "~{INT}_22") (pintype "output"))
    )
  )
)
